# MainBoard.net
KiCad netlist of a schematic drawn in EAGLE
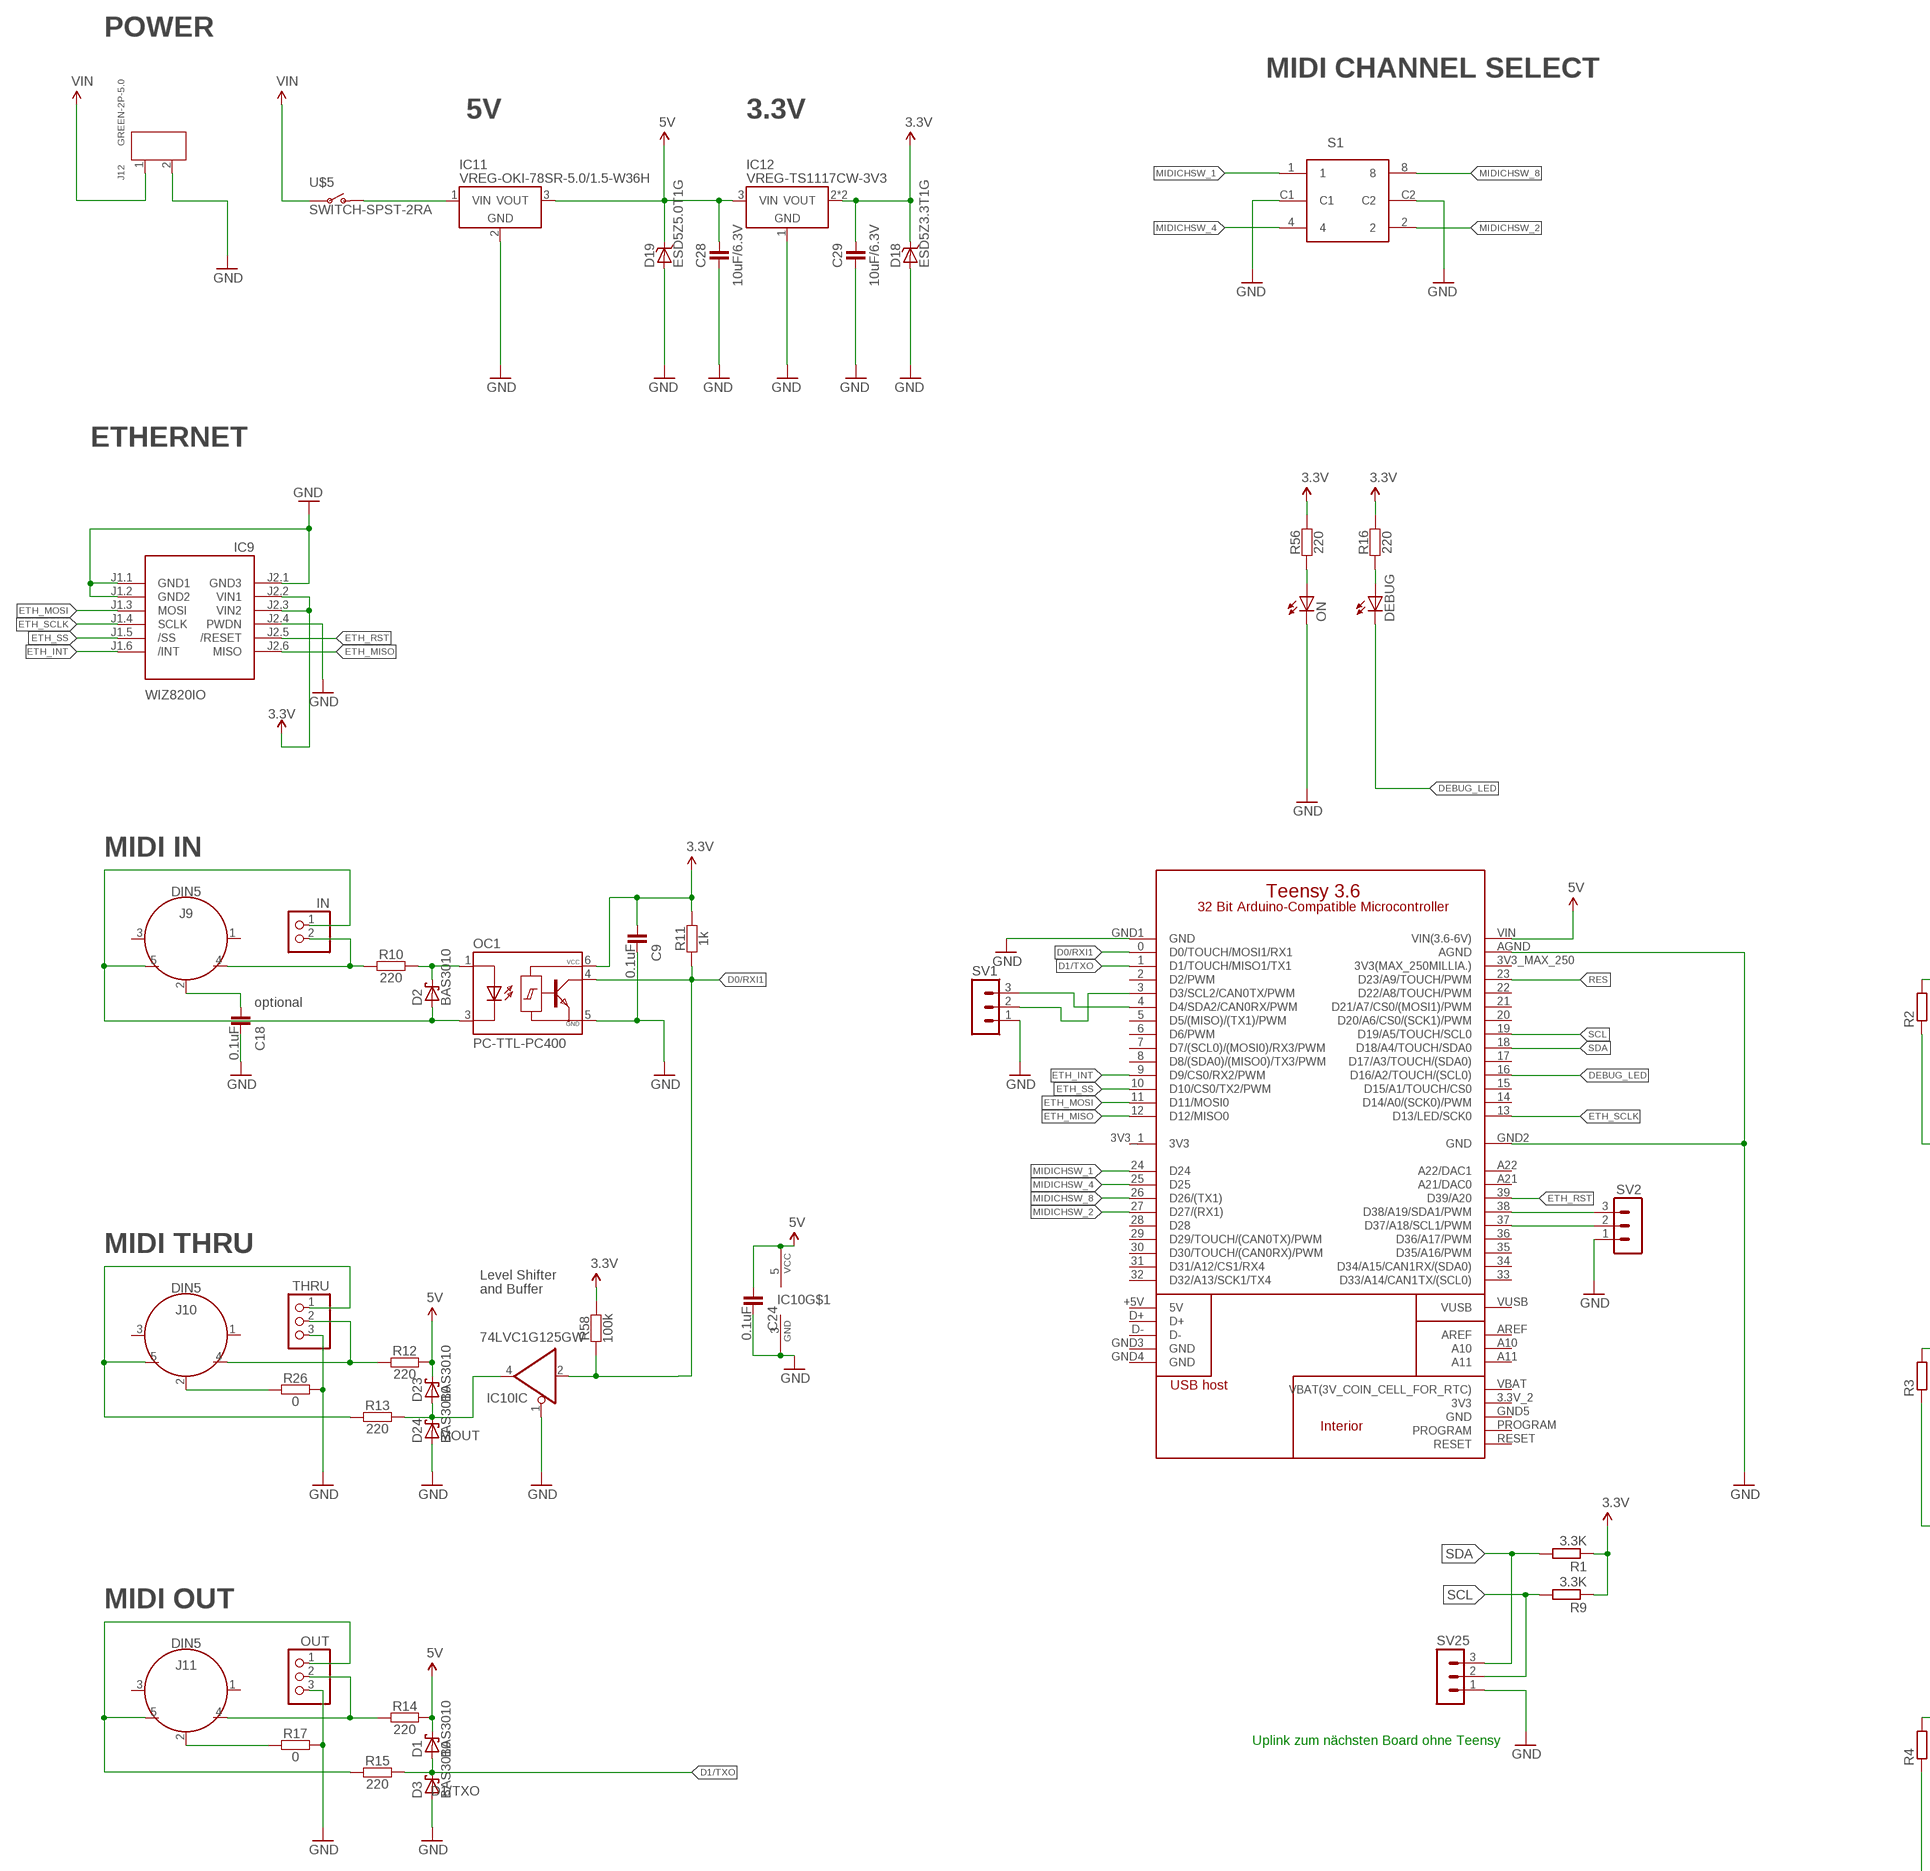
[diagram p0: schematic, sheet 1, part 1 of 2]
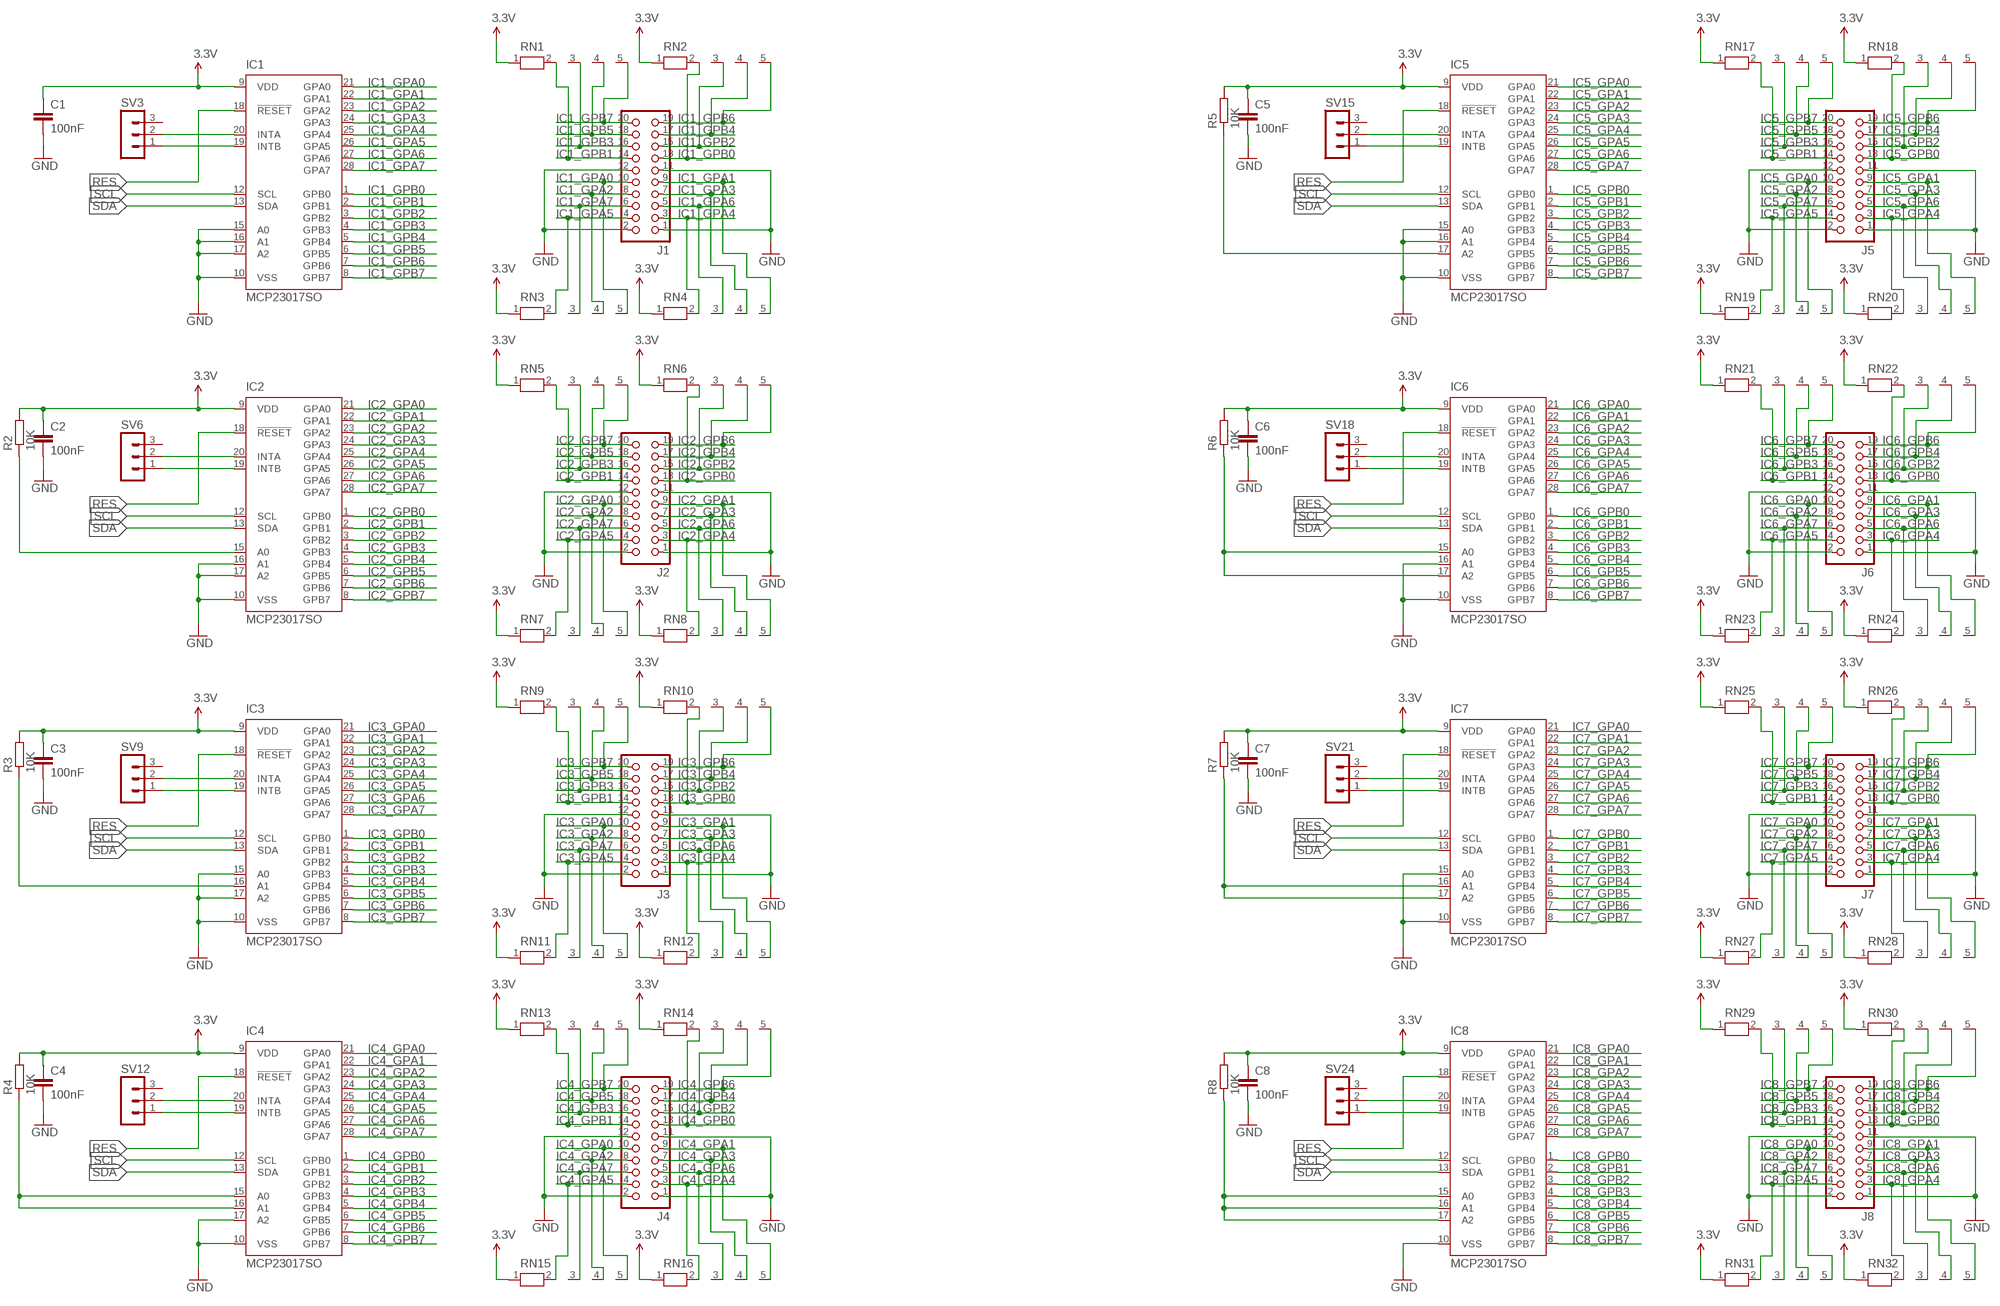
[diagram p1: schematic, sheet 1, part 2 of 2]

(export (version "E")
  (design (tool "Eeschema 10.0.6"))
  (components
    (comp (ref "C1")
      (value "100nF")
      (footprint "eagle-import:C0805")
      (libsource (lib "eagle-import") (part "C-EUC0805"))
    )
    (comp (ref "C2")
      (value "100nF")
      (footprint "eagle-import:C0805")
      (libsource (lib "eagle-import") (part "C-EUC0805"))
    )
    (comp (ref "C3")
      (value "100nF")
      (footprint "eagle-import:C0805")
      (libsource (lib "eagle-import") (part "C-EUC0805"))
    )
    (comp (ref "C4")
      (value "100nF")
      (footprint "eagle-import:C0805")
      (libsource (lib "eagle-import") (part "C-EUC0805"))
    )
    (comp (ref "C5")
      (value "100nF")
      (footprint "eagle-import:C0805")
      (libsource (lib "eagle-import") (part "C-EUC0805"))
    )
    (comp (ref "C6")
      (value "100nF")
      (footprint "eagle-import:C0805")
      (libsource (lib "eagle-import") (part "C-EUC0805"))
    )
    (comp (ref "C7")
      (value "100nF")
      (footprint "eagle-import:C0805")
      (libsource (lib "eagle-import") (part "C-EUC0805"))
    )
    (comp (ref "C8")
      (value "100nF")
      (footprint "eagle-import:C0805")
      (libsource (lib "eagle-import") (part "C-EUC0805"))
    )
    (comp (ref "C9")
      (value "0.1uF")
      (footprint "eagle-import:C0805")
      (fields (field (name "MPN") "CC0603KRX7R7BB104"))
      (libsource (lib "eagle-import") (part "CAPACITOR-0805"))
    )
    (comp (ref "C18")
      (value "0.1uF")
      (footprint "eagle-import:C0805")
      (fields (field (name "MPN") "CC0603KRX7R7BB104"))
      (libsource (lib "eagle-import") (part "CAPACITOR-0805"))
    )
    (comp (ref "C24")
      (value "0.1uF")
      (footprint "eagle-import:C0805")
      (fields (field (name "MPN") "CC0603KRX7R7BB104"))
      (libsource (lib "eagle-import") (part "CAPACITOR-0805"))
    )
    (comp (ref "C28")
      (value "10uF/6.3V")
      (footprint "eagle-import:C0805")
      (libsource (lib "eagle-import") (part "CAPACITOR-0805"))
    )
    (comp (ref "C29")
      (value "10uF/6.3V")
      (footprint "eagle-import:C0805")
      (libsource (lib "eagle-import") (part "CAPACITOR-0805"))
    )
    (comp (ref "D1")
      (value "BAS3010")
      (footprint "eagle-import:SOD323")
      (libsource (lib "eagle-import") (part "D_SCHOTTKY-SOD323"))
    )
    (comp (ref "D2")
      (value "BAS3010")
      (footprint "eagle-import:SOD323")
      (libsource (lib "eagle-import") (part "D_SCHOTTKY-SOD323"))
    )
    (comp (ref "D3")
      (value "BAS3010")
      (footprint "eagle-import:SOD323")
      (libsource (lib "eagle-import") (part "D_SCHOTTKY-SOD323"))
    )
    (comp (ref "D18")
      (value "ESD5Z3.3T1G")
      (footprint "eagle-import:SOD523")
      (libsource (lib "eagle-import") (part "D_TVS-SOD523"))
    )
    (comp (ref "D19")
      (value "ESD5Z5.0T1G")
      (footprint "eagle-import:SOD523")
      (libsource (lib "eagle-import") (part "D_TVS-SOD523"))
    )
    (comp (ref "D23")
      (value "BAS3010")
      (footprint "eagle-import:SOD323")
      (libsource (lib "eagle-import") (part "D_SCHOTTKY-SOD323"))
    )
    (comp (ref "D24")
      (value "BAS3010")
      (footprint "eagle-import:SOD323")
      (libsource (lib "eagle-import") (part "D_SCHOTTKY-SOD323"))
    )
    (comp (ref "DEBUG")
      (value "Red")
      (footprint "eagle-import:LED_3MM")
      (libsource (lib "eagle-import") (part "LED-3MM"))
    )
    (comp (ref "IC1")
      (value "MCP23017SO")
      (footprint "eagle-import:SO28W")
      (fields (field (name "MF") "MICROCHIP") (field (name "MPN") "MCP23017-E/SO"))
      (libsource (lib "eagle-import") (part "MCP23017SO"))
    )
    (comp (ref "IC2")
      (value "MCP23017SO")
      (footprint "eagle-import:SO28W")
      (fields (field (name "MF") "MICROCHIP") (field (name "MPN") "MCP23017-E/SO"))
      (libsource (lib "eagle-import") (part "MCP23017SO"))
    )
    (comp (ref "IC3")
      (value "MCP23017SO")
      (footprint "eagle-import:SO28W")
      (fields (field (name "MF") "MICROCHIP") (field (name "MPN") "MCP23017-E/SO"))
      (libsource (lib "eagle-import") (part "MCP23017SO"))
    )
    (comp (ref "IC4")
      (value "MCP23017SO")
      (footprint "eagle-import:SO28W")
      (fields (field (name "MF") "MICROCHIP") (field (name "MPN") "MCP23017-E/SO"))
      (libsource (lib "eagle-import") (part "MCP23017SO"))
    )
    (comp (ref "IC5")
      (value "MCP23017SO")
      (footprint "eagle-import:SO28W")
      (fields (field (name "MF") "MICROCHIP") (field (name "MPN") "MCP23017-E/SO"))
      (libsource (lib "eagle-import") (part "MCP23017SO"))
    )
    (comp (ref "IC6")
      (value "MCP23017SO")
      (footprint "eagle-import:SO28W")
      (fields (field (name "MF") "MICROCHIP") (field (name "MPN") "MCP23017-E/SO"))
      (libsource (lib "eagle-import") (part "MCP23017SO"))
    )
    (comp (ref "IC7")
      (value "MCP23017SO")
      (footprint "eagle-import:SO28W")
      (fields (field (name "MF") "MICROCHIP") (field (name "MPN") "MCP23017-E/SO"))
      (libsource (lib "eagle-import") (part "MCP23017SO"))
    )
    (comp (ref "IC8")
      (value "MCP23017SO")
      (footprint "eagle-import:SO28W")
      (fields (field (name "MF") "MICROCHIP") (field (name "MPN") "MCP23017-E/SO"))
      (libsource (lib "eagle-import") (part "MCP23017SO"))
    )
    (comp (ref "IC9")
      (value "WIZ820IO_DEVICE'DUAL-IN-LINE'")
      (footprint "eagle-import:WIZ820IO")
      (libsource (lib "eagle-import") (part "WIZ820IO_DEVICE'DUAL-IN-LINE'"))
    )
    (comp (ref "IC10")
      (value "74LVC1G125GW")
      (footprint "eagle-import:SOT353")
      (fields (field (name "MPN") "74HCT1G125GW,125"))
      (libsource (lib "eagle-import") (part "74HCT1G125GW"))
    )
    (comp (ref "IC11")
      (value "VREG-OKI-78SR-5.0/1.5-W36H")
      (footprint "eagle-import:OKI-78SR-H")
      (libsource (lib "eagle-import") (part "VREG-OKI-78SR-5.0/1.5-W36H"))
    )
    (comp (ref "IC12")
      (value "VREG-TS1117CW-3V3")
      (footprint "eagle-import:SOT223")
      (libsource (lib "eagle-import") (part "VREG-TS1117CW-3V3"))
    )
    (comp (ref "IN")
      (value "PINHD-1X2")
      (footprint "eagle-import:1X02")
      (libsource (lib "eagle-import") (part "PINHD-1X2"))
    )
    (comp (ref "J1")
      (value "CON_HEADER_2X10-SHROUDED")
      (footprint "eagle-import:PINSHRD_PTH_2X10")
      (libsource (lib "eagle-import") (part "CON_HEADER_2X10-SHROUDED"))
    )
    (comp (ref "J2")
      (value "CON_HEADER_2X10-SHROUDED")
      (footprint "eagle-import:PINSHRD_PTH_2X10")
      (libsource (lib "eagle-import") (part "CON_HEADER_2X10-SHROUDED"))
    )
    (comp (ref "J3")
      (value "CON_HEADER_2X10-SHROUDED")
      (footprint "eagle-import:PINSHRD_PTH_2X10")
      (libsource (lib "eagle-import") (part "CON_HEADER_2X10-SHROUDED"))
    )
    (comp (ref "J4")
      (value "CON_HEADER_2X10-SHROUDED")
      (footprint "eagle-import:PINSHRD_PTH_2X10")
      (libsource (lib "eagle-import") (part "CON_HEADER_2X10-SHROUDED"))
    )
    (comp (ref "J5")
      (value "CON_HEADER_2X10-SHROUDED")
      (footprint "eagle-import:PINSHRD_PTH_2X10")
      (libsource (lib "eagle-import") (part "CON_HEADER_2X10-SHROUDED"))
    )
    (comp (ref "J6")
      (value "CON_HEADER_2X10-SHROUDED")
      (footprint "eagle-import:PINSHRD_PTH_2X10")
      (libsource (lib "eagle-import") (part "CON_HEADER_2X10-SHROUDED"))
    )
    (comp (ref "J7")
      (value "CON_HEADER_2X10-SHROUDED")
      (footprint "eagle-import:PINSHRD_PTH_2X10")
      (libsource (lib "eagle-import") (part "CON_HEADER_2X10-SHROUDED"))
    )
    (comp (ref "J8")
      (value "CON_HEADER_2X10-SHROUDED")
      (footprint "eagle-import:PINSHRD_PTH_2X10")
      (libsource (lib "eagle-import") (part "CON_HEADER_2X10-SHROUDED"))
    )
    (comp (ref "J9")
      (value "DIN5")
      (footprint "eagle-import:DIN5-RA-PTH")
      (libsource (lib "eagle-import") (part "DIN5"))
    )
    (comp (ref "J10")
      (value "DIN5")
      (footprint "eagle-import:DIN5-RA-PTH")
      (libsource (lib "eagle-import") (part "DIN5"))
    )
    (comp (ref "J11")
      (value "DIN5")
      (footprint "eagle-import:DIN5-RA-PTH")
      (libsource (lib "eagle-import") (part "DIN5"))
    )
    (comp (ref "J12")
      (value "GREEN-2P-5.0")
      (footprint "eagle-import:H2-5.0-10.5X8.0MM")
      (libsource (lib "eagle-import") (part "SCREW-TERMINAL-GREEN(2P-5.0)"))
    )
    (comp (ref "OC1")
      (value "PC-TTL-PC400")
      (footprint "eagle-import:MINIFLAT5")
      (fields (field (name "MPN") "PC400J00000F"))
      (libsource (lib "eagle-import") (part "PC-TTL-PC400"))
    )
    (comp (ref "ON")
      (value "Red")
      (footprint "eagle-import:LED_3MM")
      (libsource (lib "eagle-import") (part "LED-3MM"))
    )
    (comp (ref "OUT")
      (value "PINHD-1X3")
      (footprint "eagle-import:1X03")
      (libsource (lib "eagle-import") (part "PINHD-1X3"))
    )
    (comp (ref "R1")
      (value "3.3K")
      (footprint "eagle-import:R0805")
      (libsource (lib "eagle-import") (part "R-EU_R0805"))
    )
    (comp (ref "R2")
      (value "10K")
      (footprint "eagle-import:R0805")
      (libsource (lib "eagle-import") (part "R-EU_R0805"))
    )
    (comp (ref "R3")
      (value "10K")
      (footprint "eagle-import:R0805")
      (libsource (lib "eagle-import") (part "R-EU_R0805"))
    )
    (comp (ref "R4")
      (value "10K")
      (footprint "eagle-import:R0805")
      (libsource (lib "eagle-import") (part "R-EU_R0805"))
    )
    (comp (ref "R5")
      (value "10K")
      (footprint "eagle-import:R0805")
      (libsource (lib "eagle-import") (part "R-EU_R0805"))
    )
    (comp (ref "R6")
      (value "10K")
      (footprint "eagle-import:R0805")
      (libsource (lib "eagle-import") (part "R-EU_R0805"))
    )
    (comp (ref "R7")
      (value "10K")
      (footprint "eagle-import:R0805")
      (libsource (lib "eagle-import") (part "R-EU_R0805"))
    )
    (comp (ref "R8")
      (value "10K")
      (footprint "eagle-import:R0805")
      (libsource (lib "eagle-import") (part "R-EU_R0805"))
    )
    (comp (ref "R9")
      (value "3.3K")
      (footprint "eagle-import:R0805")
      (libsource (lib "eagle-import") (part "R-EU_R0805"))
    )
    (comp (ref "R10")
      (value "220")
      (footprint "eagle-import:C0805")
      (libsource (lib "eagle-import") (part "RESISTOR-0805"))
    )
    (comp (ref "R11")
      (value "1k")
      (footprint "eagle-import:C0805")
      (libsource (lib "eagle-import") (part "RESISTOR-0805"))
    )
    (comp (ref "R12")
      (value "220")
      (footprint "eagle-import:C0805")
      (fields (field (name "PARTNO") "ERJ-3EKF2200V"))
      (libsource (lib "eagle-import") (part "RESISTOR-0805"))
    )
    (comp (ref "R13")
      (value "220")
      (footprint "eagle-import:C0805")
      (fields (field (name "PARTNO") "ERJ-3EKF2200V"))
      (libsource (lib "eagle-import") (part "RESISTOR-0805"))
    )
    (comp (ref "R14")
      (value "220")
      (footprint "eagle-import:C0805")
      (fields (field (name "PARTNO") "ERJ-3EKF2200V"))
      (libsource (lib "eagle-import") (part "RESISTOR-0805"))
    )
    (comp (ref "R15")
      (value "220")
      (footprint "eagle-import:C0805")
      (fields (field (name "PARTNO") "ERJ-3EKF2200V"))
      (libsource (lib "eagle-import") (part "RESISTOR-0805"))
    )
    (comp (ref "R16")
      (value "220")
      (footprint "eagle-import:C0805")
      (libsource (lib "eagle-import") (part "RESISTOR-0805"))
    )
    (comp (ref "R17")
      (value "0")
      (footprint "eagle-import:C0805")
      (libsource (lib "eagle-import") (part "RESISTOR-0805"))
    )
    (comp (ref "R26")
      (value "0")
      (footprint "eagle-import:C0805")
      (libsource (lib "eagle-import") (part "RESISTOR-0805"))
    )
    (comp (ref "R56")
      (value "220")
      (footprint "eagle-import:C0805")
      (libsource (lib "eagle-import") (part "RESISTOR-0805"))
    )
    (comp (ref "R58")
      (value "100k")
      (footprint "eagle-import:C0805")
      (libsource (lib "eagle-import") (part "RESISTOR-0805"))
    )
    (comp (ref "RN1")
      (value "RN04")
      (footprint "eagle-import:RN-5")
      (libsource (lib "eagle-import") (part "RN04"))
    )
    (comp (ref "RN2")
      (value "RN04")
      (footprint "eagle-import:RN-5")
      (libsource (lib "eagle-import") (part "RN04"))
    )
    (comp (ref "RN3")
      (value "RN04")
      (footprint "eagle-import:RN-5")
      (libsource (lib "eagle-import") (part "RN04"))
    )
    (comp (ref "RN4")
      (value "RN04")
      (footprint "eagle-import:RN-5")
      (libsource (lib "eagle-import") (part "RN04"))
    )
    (comp (ref "RN5")
      (value "RN04")
      (footprint "eagle-import:RN-5")
      (libsource (lib "eagle-import") (part "RN04"))
    )
    (comp (ref "RN6")
      (value "RN04")
      (footprint "eagle-import:RN-5")
      (libsource (lib "eagle-import") (part "RN04"))
    )
    (comp (ref "RN7")
      (value "RN04")
      (footprint "eagle-import:RN-5")
      (libsource (lib "eagle-import") (part "RN04"))
    )
    (comp (ref "RN8")
      (value "RN04")
      (footprint "eagle-import:RN-5")
      (libsource (lib "eagle-import") (part "RN04"))
    )
    (comp (ref "RN9")
      (value "RN04")
      (footprint "eagle-import:RN-5")
      (libsource (lib "eagle-import") (part "RN04"))
    )
    (comp (ref "RN10")
      (value "RN04")
      (footprint "eagle-import:RN-5")
      (libsource (lib "eagle-import") (part "RN04"))
    )
    (comp (ref "RN11")
      (value "RN04")
      (footprint "eagle-import:RN-5")
      (libsource (lib "eagle-import") (part "RN04"))
    )
    (comp (ref "RN12")
      (value "RN04")
      (footprint "eagle-import:RN-5")
      (libsource (lib "eagle-import") (part "RN04"))
    )
    (comp (ref "RN13")
      (value "RN04")
      (footprint "eagle-import:RN-5")
      (libsource (lib "eagle-import") (part "RN04"))
    )
    (comp (ref "RN14")
      (value "RN04")
      (footprint "eagle-import:RN-5")
      (libsource (lib "eagle-import") (part "RN04"))
    )
    (comp (ref "RN15")
      (value "RN04")
      (footprint "eagle-import:RN-5")
      (libsource (lib "eagle-import") (part "RN04"))
    )
    (comp (ref "RN16")
      (value "RN04")
      (footprint "eagle-import:RN-5")
      (libsource (lib "eagle-import") (part "RN04"))
    )
    (comp (ref "RN17")
      (value "RN04")
      (footprint "eagle-import:RN-5")
      (libsource (lib "eagle-import") (part "RN04"))
    )
    (comp (ref "RN18")
      (value "RN04")
      (footprint "eagle-import:RN-5")
      (libsource (lib "eagle-import") (part "RN04"))
    )
    (comp (ref "RN19")
      (value "RN04")
      (footprint "eagle-import:RN-5")
      (libsource (lib "eagle-import") (part "RN04"))
    )
    (comp (ref "RN20")
      (value "RN04")
      (footprint "eagle-import:RN-5")
      (libsource (lib "eagle-import") (part "RN04"))
    )
    (comp (ref "RN21")
      (value "RN04")
      (footprint "eagle-import:RN-5")
      (libsource (lib "eagle-import") (part "RN04"))
    )
    (comp (ref "RN22")
      (value "RN04")
      (footprint "eagle-import:RN-5")
      (libsource (lib "eagle-import") (part "RN04"))
    )
    (comp (ref "RN23")
      (value "RN04")
      (footprint "eagle-import:RN-5")
      (libsource (lib "eagle-import") (part "RN04"))
    )
    (comp (ref "RN24")
      (value "RN04")
      (footprint "eagle-import:RN-5")
      (libsource (lib "eagle-import") (part "RN04"))
    )
    (comp (ref "RN25")
      (value "RN04")
      (footprint "eagle-import:RN-5")
      (libsource (lib "eagle-import") (part "RN04"))
    )
    (comp (ref "RN26")
      (value "RN04")
      (footprint "eagle-import:RN-5")
      (libsource (lib "eagle-import") (part "RN04"))
    )
    (comp (ref "RN27")
      (value "RN04")
      (footprint "eagle-import:RN-5")
      (libsource (lib "eagle-import") (part "RN04"))
    )
    (comp (ref "RN28")
      (value "RN04")
      (footprint "eagle-import:RN-5")
      (libsource (lib "eagle-import") (part "RN04"))
    )
    (comp (ref "RN29")
      (value "RN04")
      (footprint "eagle-import:RN-5")
      (libsource (lib "eagle-import") (part "RN04"))
    )
    (comp (ref "RN30")
      (value "RN04")
      (footprint "eagle-import:RN-5")
      (libsource (lib "eagle-import") (part "RN04"))
    )
    (comp (ref "RN31")
      (value "RN04")
      (footprint "eagle-import:RN-5")
      (libsource (lib "eagle-import") (part "RN04"))
    )
    (comp (ref "RN32")
      (value "RN04")
      (footprint "eagle-import:RN-5")
      (libsource (lib "eagle-import") (part "RN04"))
    )
    (comp (ref "S1")
      (value "428521420916")
      (footprint "eagle-import:428521420916")
      (libsource (lib "eagle-import") (part "428521420916"))
    )
    (comp (ref "SV1")
      (value "MA03-1")
      (footprint "eagle-import:MA03-1")
      (libsource (lib "eagle-import") (part "MA03-1"))
    )
    (comp (ref "SV2")
      (value "MA03-1")
      (footprint "eagle-import:MA03-1")
      (libsource (lib "eagle-import") (part "MA03-1"))
    )
    (comp (ref "SV3")
      (value "MA03-1")
      (footprint "eagle-import:MA03-1")
      (libsource (lib "eagle-import") (part "MA03-1"))
    )
    (comp (ref "SV6")
      (value "MA03-1")
      (footprint "eagle-import:MA03-1")
      (libsource (lib "eagle-import") (part "MA03-1"))
    )
    (comp (ref "SV9")
      (value "MA03-1")
      (footprint "eagle-import:MA03-1")
      (libsource (lib "eagle-import") (part "MA03-1"))
    )
    (comp (ref "SV12")
      (value "MA03-1")
      (footprint "eagle-import:MA03-1")
      (libsource (lib "eagle-import") (part "MA03-1"))
    )
    (comp (ref "SV15")
      (value "MA03-1")
      (footprint "eagle-import:MA03-1")
      (libsource (lib "eagle-import") (part "MA03-1"))
    )
    (comp (ref "SV18")
      (value "MA03-1")
      (footprint "eagle-import:MA03-1")
      (libsource (lib "eagle-import") (part "MA03-1"))
    )
    (comp (ref "SV21")
      (value "MA03-1")
      (footprint "eagle-import:MA03-1")
      (libsource (lib "eagle-import") (part "MA03-1"))
    )
    (comp (ref "SV24")
      (value "MA03-1")
      (footprint "eagle-import:MA03-1")
      (libsource (lib "eagle-import") (part "MA03-1"))
    )
    (comp (ref "SV25")
      (value "MA03-1")
      (footprint "eagle-import:MA03-1")
      (libsource (lib "eagle-import") (part "MA03-1"))
    )
    (comp (ref "THRU")
      (value "PINHD-1X3")
      (footprint "eagle-import:1X03")
      (libsource (lib "eagle-import") (part "PINHD-1X3"))
    )
    (comp (ref "U$1")
      (value "TEENSY-3.6_ONLY_HOLES")
      (footprint "eagle-import:TEENSY-3.6_ONLY_HOLES")
      (libsource (lib "eagle-import") (part "TEENSY-3.6_ONLY_HOLES"))
    )
    (comp (ref "U$5")
      (value "SWITCH-SPST-2RA")
      (footprint "eagle-import:R_SW_TH")
      (libsource (lib "eagle-import") (part "SWITCH-SPST-2RA"))
    )
  )
  (nets
    (net (code "1") (name "/3V3") (class "Default")
      (node (ref "U$1") (pin "3V3_1") (pinfunction "3V3_3V3_1") (pintype "power_in"))
    )
    (net (code "2") (name "/IC1_GPA0") (class "Default")
      (node (ref "IC1") (pin "21") (pinfunction "GPA0_21") (pintype "bidirectional"))
      (node (ref "J1") (pin "10") (pinfunction "10_10") (pintype "passive"))
      (node (ref "RN3") (pin "5") (pinfunction "5_5") (pintype "passive"))
    )
    (net (code "3") (name "/IC1_GPA1") (class "Default")
      (node (ref "IC1") (pin "22") (pinfunction "GPA1_22") (pintype "bidirectional"))
      (node (ref "J1") (pin "9") (pinfunction "9_9") (pintype "passive"))
      (node (ref "RN4") (pin "5") (pinfunction "5_5") (pintype "passive"))
    )
    (net (code "4") (name "/IC1_GPA2") (class "Default")
      (node (ref "IC1") (pin "23") (pinfunction "GPA2_23") (pintype "bidirectional"))
      (node (ref "J1") (pin "8") (pinfunction "8_8") (pintype "passive"))
      (node (ref "RN3") (pin "4") (pinfunction "4_4") (pintype "passive"))
    )
    (net (code "5") (name "/IC1_GPA3") (class "Default")
      (node (ref "IC1") (pin "24") (pinfunction "GPA3_24") (pintype "bidirectional"))
      (node (ref "J1") (pin "7") (pinfunction "7_7") (pintype "passive"))
      (node (ref "RN4") (pin "4") (pinfunction "4_4") (pintype "passive"))
    )
    (net (code "6") (name "/IC1_GPA4") (class "Default")
      (node (ref "IC1") (pin "25") (pinfunction "GPA4_25") (pintype "bidirectional"))
      (node (ref "J1") (pin "3") (pinfunction "3_3") (pintype "passive"))
      (node (ref "RN4") (pin "2") (pinfunction "2_2") (pintype "passive"))
    )
    (net (code "7") (name "/IC1_GPA5") (class "Default")
      (node (ref "IC1") (pin "26") (pinfunction "GPA5_26") (pintype "bidirectional"))
      (node (ref "J1") (pin "4") (pinfunction "4_4") (pintype "passive"))
      (node (ref "RN3") (pin "2") (pinfunction "2_2") (pintype "passive"))
    )
    (net (code "8") (name "/IC1_GPA6") (class "Default")
      (node (ref "IC1") (pin "27") (pinfunction "GPA6_27") (pintype "bidirectional"))
      (node (ref "J1") (pin "5") (pinfunction "5_5") (pintype "passive"))
      (node (ref "RN4") (pin "3") (pinfunction "3_3") (pintype "passive"))
    )
    (net (code "9") (name "/IC1_GPA7") (class "Default")
      (node (ref "IC1") (pin "28") (pinfunction "GPA7_28") (pintype "bidirectional"))
      (node (ref "J1") (pin "6") (pinfunction "6_6") (pintype "passive"))
      (node (ref "RN3") (pin "3") (pinfunction "3_3") (pintype "passive"))
    )
    (net (code "10") (name "/IC1_GPB0") (class "Default")
      (node (ref "IC1") (pin "1") (pinfunction "GPB0_1") (pintype "bidirectional"))
      (node (ref "J1") (pin "13") (pinfunction "13_13") (pintype "passive"))
      (node (ref "RN2") (pin "2") (pinfunction "2_2") (pintype "passive"))
    )
    (net (code "11") (name "/IC1_GPB1") (class "Default")
      (node (ref "IC1") (pin "2") (pinfunction "GPB1_2") (pintype "bidirectional"))
      (node (ref "J1") (pin "14") (pinfunction "14_14") (pintype "passive"))
      (node (ref "RN1") (pin "2") (pinfunction "2_2") (pintype "passive"))
    )
    (net (code "12") (name "/IC1_GPB2") (class "Default")
      (node (ref "IC1") (pin "3") (pinfunction "GPB2_3") (pintype "bidirectional"))
      (node (ref "J1") (pin "15") (pinfunction "15_15") (pintype "passive"))
      (node (ref "RN2") (pin "3") (pinfunction "3_3") (pintype "passive"))
    )
    (net (code "13") (name "/IC1_GPB3") (class "Default")
      (node (ref "IC1") (pin "4") (pinfunction "GPB3_4") (pintype "bidirectional"))
      (node (ref "J1") (pin "16") (pinfunction "16_16") (pintype "passive"))
      (node (ref "RN1") (pin "3") (pinfunction "3_3") (pintype "passive"))
    )
    (net (code "14") (name "/IC1_GPB4") (class "Default")
      (node (ref "IC1") (pin "5") (pinfunction "GPB4_5") (pintype "bidirectional"))
      (node (ref "J1") (pin "17") (pinfunction "17_17") (pintype "passive"))
      (node (ref "RN2") (pin "4") (pinfunction "4_4") (pintype "passive"))
    )
    (net (code "15") (name "/IC1_GPB5") (class "Default")
      (node (ref "IC1") (pin "6") (pinfunction "GPB5_6") (pintype "bidirectional"))
      (node (ref "J1") (pin "18") (pinfunction "18_18") (pintype "passive"))
      (node (ref "RN1") (pin "4") (pinfunction "4_4") (pintype "passive"))
    )
    (net (code "16") (name "/IC1_GPB6") (class "Default")
      (node (ref "IC1") (pin "7") (pinfunction "GPB6_7") (pintype "bidirectional"))
      (node (ref "J1") (pin "19") (pinfunction "19_19") (pintype "passive"))
      (node (ref "RN2") (pin "5") (pinfunction "5_5") (pintype "passive"))
    )
    (net (code "17") (name "/IC1_GPB7") (class "Default")
      (node (ref "IC1") (pin "8") (pinfunction "GPB7_8") (pintype "bidirectional"))
      (node (ref "J1") (pin "20") (pinfunction "20_20") (pintype "passive"))
      (node (ref "RN1") (pin "5") (pinfunction "5_5") (pintype "passive"))
    )
    (net (code "18") (name "/IC2_GPA0") (class "Default")
      (node (ref "IC2") (pin "21") (pinfunction "GPA0_21") (pintype "bidirectional"))
      (node (ref "J2") (pin "10") (pinfunction "10_10") (pintype "passive"))
      (node (ref "RN7") (pin "5") (pinfunction "5_5") (pintype "passive"))
    )
    (net (code "19") (name "/IC2_GPA1") (class "Default")
      (node (ref "IC2") (pin "22") (pinfunction "GPA1_22") (pintype "bidirectional"))
      (node (ref "J2") (pin "9") (pinfunction "9_9") (pintype "passive"))
      (node (ref "RN8") (pin "5") (pinfunction "5_5") (pintype "passive"))
    )
    (net (code "20") (name "/IC2_GPA2") (class "Default")
      (node (ref "IC2") (pin "23") (pinfunction "GPA2_23") (pintype "bidirectional"))
      (node (ref "J2") (pin "8") (pinfunction "8_8") (pintype "passive"))
      (node (ref "RN7") (pin "4") (pinfunction "4_4") (pintype "passive"))
    )
    (net (code "21") (name "/IC2_GPA3") (class "Default")
      (node (ref "IC2") (pin "24") (pinfunction "GPA3_24") (pintype "bidirectional"))
      (node (ref "J2") (pin "7") (pinfunction "7_7") (pintype "passive"))
      (node (ref "RN8") (pin "4") (pinfunction "4_4") (pintype "passive"))
    )
    (net (code "22") (name "/IC2_GPA4") (class "Default")
      (node (ref "IC2") (pin "25") (pinfunction "GPA4_25") (pintype "bidirectional"))
      (node (ref "J2") (pin "3") (pinfunction "3_3") (pintype "passive"))
      (node (ref "RN8") (pin "2") (pinfunction "2_2") (pintype "passive"))
    )
    (net (code "23") (name "/IC2_GPA5") (class "Default")
      (node (ref "IC2") (pin "26") (pinfunction "GPA5_26") (pintype "bidirectional"))
      (node (ref "J2") (pin "4") (pinfunction "4_4") (pintype "passive"))
      (node (ref "RN7") (pin "2") (pinfunction "2_2") (pintype "passive"))
    )
    (net (code "24") (name "/IC2_GPA6") (class "Default")
      (node (ref "IC2") (pin "27") (pinfunction "GPA6_27") (pintype "bidirectional"))
      (node (ref "J2") (pin "5") (pinfunction "5_5") (pintype "passive"))
      (node (ref "RN8") (pin "3") (pinfunction "3_3") (pintype "passive"))
    )
    (net (code "25") (name "/IC2_GPA7") (class "Default")
      (node (ref "IC2") (pin "28") (pinfunction "GPA7_28") (pintype "bidirectional"))
      (node (ref "J2") (pin "6") (pinfunction "6_6") (pintype "passive"))
      (node (ref "RN7") (pin "3") (pinfunction "3_3") (pintype "passive"))
    )
    (net (code "26") (name "/IC2_GPB0") (class "Default")
      (node (ref "IC2") (pin "1") (pinfunction "GPB0_1") (pintype "bidirectional"))
      (node (ref "J2") (pin "13") (pinfunction "13_13") (pintype "passive"))
      (node (ref "RN6") (pin "2") (pinfunction "2_2") (pintype "passive"))
    )
    (net (code "27") (name "/IC2_GPB1") (class "Default")
      (node (ref "IC2") (pin "2") (pinfunction "GPB1_2") (pintype "bidirectional"))
      (node (ref "J2") (pin "14") (pinfunction "14_14") (pintype "passive"))
      (node (ref "RN5") (pin "2") (pinfunction "2_2") (pintype "passive"))
    )
    (net (code "28") (name "/IC2_GPB2") (class "Default")
      (node (ref "IC2") (pin "3") (pinfunction "GPB2_3") (pintype "bidirectional"))
      (node (ref "J2") (pin "15") (pinfunction "15_15") (pintype "passive"))
      (node (ref "RN6") (pin "3") (pinfunction "3_3") (pintype "passive"))
    )
    (net (code "29") (name "/IC2_GPB3") (class "Default")
      (node (ref "IC2") (pin "4") (pinfunction "GPB3_4") (pintype "bidirectional"))
      (node (ref "J2") (pin "16") (pinfunction "16_16") (pintype "passive"))
      (node (ref "RN5") (pin "3") (pinfunction "3_3") (pintype "passive"))
    )
    (net (code "30") (name "/IC2_GPB4") (class "Default")
      (node (ref "IC2") (pin "5") (pinfunction "GPB4_5") (pintype "bidirectional"))
      (node (ref "J2") (pin "17") (pinfunction "17_17") (pintype "passive"))
      (node (ref "RN6") (pin "4") (pinfunction "4_4") (pintype "passive"))
    )
    (net (code "31") (name "/IC2_GPB5") (class "Default")
      (node (ref "IC2") (pin "6") (pinfunction "GPB5_6") (pintype "bidirectional"))
      (node (ref "J2") (pin "18") (pinfunction "18_18") (pintype "passive"))
      (node (ref "RN5") (pin "4") (pinfunction "4_4") (pintype "passive"))
    )
    (net (code "32") (name "/IC2_GPB6") (class "Default")
      (node (ref "IC2") (pin "7") (pinfunction "GPB6_7") (pintype "bidirectional"))
      (node (ref "J2") (pin "19") (pinfunction "19_19") (pintype "passive"))
      (node (ref "RN6") (pin "5") (pinfunction "5_5") (pintype "passive"))
    )
    (net (code "33") (name "/IC2_GPB7") (class "Default")
      (node (ref "IC2") (pin "8") (pinfunction "GPB7_8") (pintype "bidirectional"))
      (node (ref "J2") (pin "20") (pinfunction "20_20") (pintype "passive"))
      (node (ref "RN5") (pin "5") (pinfunction "5_5") (pintype "passive"))
    )
    (net (code "34") (name "/IC3_GPA0") (class "Default")
      (node (ref "IC3") (pin "21") (pinfunction "GPA0_21") (pintype "bidirectional"))
      (node (ref "J3") (pin "10") (pinfunction "10_10") (pintype "passive"))
      (node (ref "RN11") (pin "5") (pinfunction "5_5") (pintype "passive"))
    )
    (net (code "35") (name "/IC3_GPA1") (class "Default")
      (node (ref "IC3") (pin "22") (pinfunction "GPA1_22") (pintype "bidirectional"))
      (node (ref "J3") (pin "9") (pinfunction "9_9") (pintype "passive"))
      (node (ref "RN12") (pin "5") (pinfunction "5_5") (pintype "passive"))
    )
    (net (code "36") (name "/IC3_GPA2") (class "Default")
      (node (ref "IC3") (pin "23") (pinfunction "GPA2_23") (pintype "bidirectional"))
      (node (ref "J3") (pin "8") (pinfunction "8_8") (pintype "passive"))
      (node (ref "RN11") (pin "4") (pinfunction "4_4") (pintype "passive"))
    )
    (net (code "37") (name "/IC3_GPA3") (class "Default")
      (node (ref "IC3") (pin "24") (pinfunction "GPA3_24") (pintype "bidirectional"))
      (node (ref "J3") (pin "7") (pinfunction "7_7") (pintype "passive"))
      (node (ref "RN12") (pin "4") (pinfunction "4_4") (pintype "passive"))
    )
    (net (code "38") (name "/IC3_GPA4") (class "Default")
      (node (ref "IC3") (pin "25") (pinfunction "GPA4_25") (pintype "bidirectional"))
      (node (ref "J3") (pin "3") (pinfunction "3_3") (pintype "passive"))
      (node (ref "RN12") (pin "2") (pinfunction "2_2") (pintype "passive"))
    )
    (net (code "39") (name "/IC3_GPA5") (class "Default")
      (node (ref "IC3") (pin "26") (pinfunction "GPA5_26") (pintype "bidirectional"))
      (node (ref "J3") (pin "4") (pinfunction "4_4") (pintype "passive"))
      (node (ref "RN11") (pin "2") (pinfunction "2_2") (pintype "passive"))
    )
    (net (code "40") (name "/IC3_GPA6") (class "Default")
      (node (ref "IC3") (pin "27") (pinfunction "GPA6_27") (pintype "bidirectional"))
      (node (ref "J3") (pin "5") (pinfunction "5_5") (pintype "passive"))
      (node (ref "RN12") (pin "3") (pinfunction "3_3") (pintype "passive"))
    )
    (net (code "41") (name "/IC3_GPA7") (class "Default")
      (node (ref "IC3") (pin "28") (pinfunction "GPA7_28") (pintype "bidirectional"))
      (node (ref "J3") (pin "6") (pinfunction "6_6") (pintype "passive"))
      (node (ref "RN11") (pin "3") (pinfunction "3_3") (pintype "passive"))
    )
    (net (code "42") (name "/IC3_GPB0") (class "Default")
      (node (ref "IC3") (pin "1") (pinfunction "GPB0_1") (pintype "bidirectional"))
      (node (ref "J3") (pin "13") (pinfunction "13_13") (pintype "passive"))
      (node (ref "RN10") (pin "2") (pinfunction "2_2") (pintype "passive"))
    )
    (net (code "43") (name "/IC3_GPB1") (class "Default")
      (node (ref "IC3") (pin "2") (pinfunction "GPB1_2") (pintype "bidirectional"))
      (node (ref "J3") (pin "14") (pinfunction "14_14") (pintype "passive"))
      (node (ref "RN9") (pin "2") (pinfunction "2_2") (pintype "passive"))
    )
    (net (code "44") (name "/IC3_GPB2") (class "Default")
      (node (ref "IC3") (pin "3") (pinfunction "GPB2_3") (pintype "bidirectional"))
      (node (ref "J3") (pin "15") (pinfunction "15_15") (pintype "passive"))
      (node (ref "RN10") (pin "3") (pinfunction "3_3") (pintype "passive"))
    )
    (net (code "45") (name "/IC3_GPB3") (class "Default")
      (node (ref "IC3") (pin "4") (pinfunction "GPB3_4") (pintype "bidirectional"))
      (node (ref "J3") (pin "16") (pinfunction "16_16") (pintype "passive"))
      (node (ref "RN9") (pin "3") (pinfunction "3_3") (pintype "passive"))
    )
    (net (code "46") (name "/IC3_GPB4") (class "Default")
      (node (ref "IC3") (pin "5") (pinfunction "GPB4_5") (pintype "bidirectional"))
      (node (ref "J3") (pin "17") (pinfunction "17_17") (pintype "passive"))
      (node (ref "RN10") (pin "4") (pinfunction "4_4") (pintype "passive"))
    )
    (net (code "47") (name "/IC3_GPB5") (class "Default")
      (node (ref "IC3") (pin "6") (pinfunction "GPB5_6") (pintype "bidirectional"))
      (node (ref "J3") (pin "18") (pinfunction "18_18") (pintype "passive"))
      (node (ref "RN9") (pin "4") (pinfunction "4_4") (pintype "passive"))
    )
    (net (code "48") (name "/IC3_GPB6") (class "Default")
      (node (ref "IC3") (pin "7") (pinfunction "GPB6_7") (pintype "bidirectional"))
      (node (ref "J3") (pin "19") (pinfunction "19_19") (pintype "passive"))
      (node (ref "RN10") (pin "5") (pinfunction "5_5") (pintype "passive"))
    )
    (net (code "49") (name "/IC3_GPB7") (class "Default")
      (node (ref "IC3") (pin "8") (pinfunction "GPB7_8") (pintype "bidirectional"))
      (node (ref "J3") (pin "20") (pinfunction "20_20") (pintype "passive"))
      (node (ref "RN9") (pin "5") (pinfunction "5_5") (pintype "passive"))
    )
    (net (code "50") (name "/IC4_GPA0") (class "Default")
      (node (ref "IC4") (pin "21") (pinfunction "GPA0_21") (pintype "bidirectional"))
      (node (ref "J4") (pin "10") (pinfunction "10_10") (pintype "passive"))
      (node (ref "RN15") (pin "5") (pinfunction "5_5") (pintype "passive"))
    )
    (net (code "51") (name "/IC4_GPA1") (class "Default")
      (node (ref "IC4") (pin "22") (pinfunction "GPA1_22") (pintype "bidirectional"))
      (node (ref "J4") (pin "9") (pinfunction "9_9") (pintype "passive"))
      (node (ref "RN16") (pin "5") (pinfunction "5_5") (pintype "passive"))
    )
    (net (code "52") (name "/IC4_GPA2") (class "Default")
      (node (ref "IC4") (pin "23") (pinfunction "GPA2_23") (pintype "bidirectional"))
      (node (ref "J4") (pin "8") (pinfunction "8_8") (pintype "passive"))
      (node (ref "RN15") (pin "4") (pinfunction "4_4") (pintype "passive"))
    )
    (net (code "53") (name "/IC4_GPA3") (class "Default")
      (node (ref "IC4") (pin "24") (pinfunction "GPA3_24") (pintype "bidirectional"))
      (node (ref "J4") (pin "7") (pinfunction "7_7") (pintype "passive"))
      (node (ref "RN16") (pin "4") (pinfunction "4_4") (pintype "passive"))
    )
    (net (code "54") (name "/IC4_GPA4") (class "Default")
      (node (ref "IC4") (pin "25") (pinfunction "GPA4_25") (pintype "bidirectional"))
      (node (ref "J4") (pin "3") (pinfunction "3_3") (pintype "passive"))
      (node (ref "RN16") (pin "2") (pinfunction "2_2") (pintype "passive"))
    )
    (net (code "55") (name "/IC4_GPA5") (class "Default")
      (node (ref "IC4") (pin "26") (pinfunction "GPA5_26") (pintype "bidirectional"))
      (node (ref "J4") (pin "4") (pinfunction "4_4") (pintype "passive"))
      (node (ref "RN15") (pin "2") (pinfunction "2_2") (pintype "passive"))
    )
    (net (code "56") (name "/IC4_GPA6") (class "Default")
      (node (ref "IC4") (pin "27") (pinfunction "GPA6_27") (pintype "bidirectional"))
      (node (ref "J4") (pin "5") (pinfunction "5_5") (pintype "passive"))
      (node (ref "RN16") (pin "3") (pinfunction "3_3") (pintype "passive"))
    )
    (net (code "57") (name "/IC4_GPA7") (class "Default")
      (node (ref "IC4") (pin "28") (pinfunction "GPA7_28") (pintype "bidirectional"))
      (node (ref "J4") (pin "6") (pinfunction "6_6") (pintype "passive"))
      (node (ref "RN15") (pin "3") (pinfunction "3_3") (pintype "passive"))
    )
    (net (code "58") (name "/IC4_GPB0") (class "Default")
      (node (ref "IC4") (pin "1") (pinfunction "GPB0_1") (pintype "bidirectional"))
      (node (ref "J4") (pin "13") (pinfunction "13_13") (pintype "passive"))
      (node (ref "RN14") (pin "2") (pinfunction "2_2") (pintype "passive"))
    )
    (net (code "59") (name "/IC4_GPB1") (class "Default")
      (node (ref "IC4") (pin "2") (pinfunction "GPB1_2") (pintype "bidirectional"))
      (node (ref "J4") (pin "14") (pinfunction "14_14") (pintype "passive"))
      (node (ref "RN13") (pin "2") (pinfunction "2_2") (pintype "passive"))
    )
    (net (code "60") (name "/IC4_GPB2") (class "Default")
      (node (ref "IC4") (pin "3") (pinfunction "GPB2_3") (pintype "bidirectional"))
      (node (ref "J4") (pin "15") (pinfunction "15_15") (pintype "passive"))
      (node (ref "RN14") (pin "3") (pinfunction "3_3") (pintype "passive"))
    )
    (net (code "61") (name "/IC4_GPB3") (class "Default")
      (node (ref "IC4") (pin "4") (pinfunction "GPB3_4") (pintype "bidirectional"))
      (node (ref "J4") (pin "16") (pinfunction "16_16") (pintype "passive"))
      (node (ref "RN13") (pin "3") (pinfunction "3_3") (pintype "passive"))
    )
    (net (code "62") (name "/IC4_GPB4") (class "Default")
      (node (ref "IC4") (pin "5") (pinfunction "GPB4_5") (pintype "bidirectional"))
      (node (ref "J4") (pin "17") (pinfunction "17_17") (pintype "passive"))
      (node (ref "RN14") (pin "4") (pinfunction "4_4") (pintype "passive"))
    )
    (net (code "63") (name "/IC4_GPB5") (class "Default")
      (node (ref "IC4") (pin "6") (pinfunction "GPB5_6") (pintype "bidirectional"))
      (node (ref "J4") (pin "18") (pinfunction "18_18") (pintype "passive"))
      (node (ref "RN13") (pin "4") (pinfunction "4_4") (pintype "passive"))
    )
    (net (code "64") (name "/IC4_GPB6") (class "Default")
      (node (ref "IC4") (pin "7") (pinfunction "GPB6_7") (pintype "bidirectional"))
      (node (ref "J4") (pin "19") (pinfunction "19_19") (pintype "passive"))
      (node (ref "RN14") (pin "5") (pinfunction "5_5") (pintype "passive"))
    )
    (net (code "65") (name "/IC4_GPB7") (class "Default")
      (node (ref "IC4") (pin "8") (pinfunction "GPB7_8") (pintype "bidirectional"))
      (node (ref "J4") (pin "20") (pinfunction "20_20") (pintype "passive"))
      (node (ref "RN13") (pin "5") (pinfunction "5_5") (pintype "passive"))
    )
    (net (code "66") (name "/IC5_GPA0") (class "Default")
      (node (ref "IC5") (pin "21") (pinfunction "GPA0_21") (pintype "bidirectional"))
      (node (ref "J5") (pin "10") (pinfunction "10_10") (pintype "passive"))
      (node (ref "RN19") (pin "5") (pinfunction "5_5") (pintype "passive"))
    )
    (net (code "67") (name "/IC5_GPA1") (class "Default")
      (node (ref "IC5") (pin "22") (pinfunction "GPA1_22") (pintype "bidirectional"))
      (node (ref "J5") (pin "9") (pinfunction "9_9") (pintype "passive"))
      (node (ref "RN20") (pin "5") (pinfunction "5_5") (pintype "passive"))
    )
    (net (code "68") (name "/IC5_GPA2") (class "Default")
      (node (ref "IC5") (pin "23") (pinfunction "GPA2_23") (pintype "bidirectional"))
      (node (ref "J5") (pin "8") (pinfunction "8_8") (pintype "passive"))
      (node (ref "RN19") (pin "4") (pinfunction "4_4") (pintype "passive"))
    )
    (net (code "69") (name "/IC5_GPA3") (class "Default")
      (node (ref "IC5") (pin "24") (pinfunction "GPA3_24") (pintype "bidirectional"))
      (node (ref "J5") (pin "7") (pinfunction "7_7") (pintype "passive"))
      (node (ref "RN20") (pin "4") (pinfunction "4_4") (pintype "passive"))
    )
    (net (code "70") (name "/IC5_GPA4") (class "Default")
      (node (ref "IC5") (pin "25") (pinfunction "GPA4_25") (pintype "bidirectional"))
      (node (ref "J5") (pin "3") (pinfunction "3_3") (pintype "passive"))
      (node (ref "RN20") (pin "2") (pinfunction "2_2") (pintype "passive"))
    )
    (net (code "71") (name "/IC5_GPA5") (class "Default")
      (node (ref "IC5") (pin "26") (pinfunction "GPA5_26") (pintype "bidirectional"))
      (node (ref "J5") (pin "4") (pinfunction "4_4") (pintype "passive"))
      (node (ref "RN19") (pin "2") (pinfunction "2_2") (pintype "passive"))
    )
    (net (code "72") (name "/IC5_GPA6") (class "Default")
      (node (ref "IC5") (pin "27") (pinfunction "GPA6_27") (pintype "bidirectional"))
      (node (ref "J5") (pin "5") (pinfunction "5_5") (pintype "passive"))
      (node (ref "RN20") (pin "3") (pinfunction "3_3") (pintype "passive"))
    )
    (net (code "73") (name "/IC5_GPA7") (class "Default")
      (node (ref "IC5") (pin "28") (pinfunction "GPA7_28") (pintype "bidirectional"))
      (node (ref "J5") (pin "6") (pinfunction "6_6") (pintype "passive"))
      (node (ref "RN19") (pin "3") (pinfunction "3_3") (pintype "passive"))
    )
    (net (code "74") (name "/IC5_GPB0") (class "Default")
      (node (ref "IC5") (pin "1") (pinfunction "GPB0_1") (pintype "bidirectional"))
      (node (ref "J5") (pin "13") (pinfunction "13_13") (pintype "passive"))
      (node (ref "RN18") (pin "2") (pinfunction "2_2") (pintype "passive"))
    )
    (net (code "75") (name "/IC5_GPB1") (class "Default")
      (node (ref "IC5") (pin "2") (pinfunction "GPB1_2") (pintype "bidirectional"))
      (node (ref "J5") (pin "14") (pinfunction "14_14") (pintype "passive"))
      (node (ref "RN17") (pin "2") (pinfunction "2_2") (pintype "passive"))
    )
    (net (code "76") (name "/IC5_GPB2") (class "Default")
      (node (ref "IC5") (pin "3") (pinfunction "GPB2_3") (pintype "bidirectional"))
      (node (ref "J5") (pin "15") (pinfunction "15_15") (pintype "passive"))
      (node (ref "RN18") (pin "3") (pinfunction "3_3") (pintype "passive"))
    )
    (net (code "77") (name "/IC5_GPB3") (class "Default")
      (node (ref "IC5") (pin "4") (pinfunction "GPB3_4") (pintype "bidirectional"))
      (node (ref "J5") (pin "16") (pinfunction "16_16") (pintype "passive"))
      (node (ref "RN17") (pin "3") (pinfunction "3_3") (pintype "passive"))
    )
    (net (code "78") (name "/IC5_GPB4") (class "Default")
      (node (ref "IC5") (pin "5") (pinfunction "GPB4_5") (pintype "bidirectional"))
      (node (ref "J5") (pin "17") (pinfunction "17_17") (pintype "passive"))
      (node (ref "RN18") (pin "4") (pinfunction "4_4") (pintype "passive"))
    )
    (net (code "79") (name "/IC5_GPB5") (class "Default")
      (node (ref "IC5") (pin "6") (pinfunction "GPB5_6") (pintype "bidirectional"))
      (node (ref "J5") (pin "18") (pinfunction "18_18") (pintype "passive"))
      (node (ref "RN17") (pin "4") (pinfunction "4_4") (pintype "passive"))
    )
    (net (code "80") (name "/IC5_GPB6") (class "Default")
      (node (ref "IC5") (pin "7") (pinfunction "GPB6_7") (pintype "bidirectional"))
      (node (ref "J5") (pin "19") (pinfunction "19_19") (pintype "passive"))
      (node (ref "RN18") (pin "5") (pinfunction "5_5") (pintype "passive"))
    )
    (net (code "81") (name "/IC5_GPB7") (class "Default")
      (node (ref "IC5") (pin "8") (pinfunction "GPB7_8") (pintype "bidirectional"))
      (node (ref "J5") (pin "20") (pinfunction "20_20") (pintype "passive"))
      (node (ref "RN17") (pin "5") (pinfunction "5_5") (pintype "passive"))
    )
    (net (code "82") (name "/IC6_GPA0") (class "Default")
      (node (ref "IC6") (pin "21") (pinfunction "GPA0_21") (pintype "bidirectional"))
      (node (ref "J6") (pin "10") (pinfunction "10_10") (pintype "passive"))
      (node (ref "RN23") (pin "5") (pinfunction "5_5") (pintype "passive"))
    )
    (net (code "83") (name "/IC6_GPA1") (class "Default")
      (node (ref "IC6") (pin "22") (pinfunction "GPA1_22") (pintype "bidirectional"))
      (node (ref "J6") (pin "9") (pinfunction "9_9") (pintype "passive"))
      (node (ref "RN24") (pin "5") (pinfunction "5_5") (pintype "passive"))
    )
    (net (code "84") (name "/IC6_GPA2") (class "Default")
      (node (ref "IC6") (pin "23") (pinfunction "GPA2_23") (pintype "bidirectional"))
      (node (ref "J6") (pin "8") (pinfunction "8_8") (pintype "passive"))
      (node (ref "RN23") (pin "4") (pinfunction "4_4") (pintype "passive"))
    )
    (net (code "85") (name "/IC6_GPA3") (class "Default")
      (node (ref "IC6") (pin "24") (pinfunction "GPA3_24") (pintype "bidirectional"))
      (node (ref "J6") (pin "7") (pinfunction "7_7") (pintype "passive"))
      (node (ref "RN24") (pin "4") (pinfunction "4_4") (pintype "passive"))
    )
    (net (code "86") (name "/IC6_GPA4") (class "Default")
      (node (ref "IC6") (pin "25") (pinfunction "GPA4_25") (pintype "bidirectional"))
      (node (ref "J6") (pin "3") (pinfunction "3_3") (pintype "passive"))
      (node (ref "RN24") (pin "2") (pinfunction "2_2") (pintype "passive"))
    )
    (net (code "87") (name "/IC6_GPA5") (class "Default")
      (node (ref "IC6") (pin "26") (pinfunction "GPA5_26") (pintype "bidirectional"))
      (node (ref "J6") (pin "4") (pinfunction "4_4") (pintype "passive"))
      (node (ref "RN23") (pin "2") (pinfunction "2_2") (pintype "passive"))
    )
    (net (code "88") (name "/IC6_GPA6") (class "Default")
      (node (ref "IC6") (pin "27") (pinfunction "GPA6_27") (pintype "bidirectional"))
      (node (ref "J6") (pin "5") (pinfunction "5_5") (pintype "passive"))
      (node (ref "RN24") (pin "3") (pinfunction "3_3") (pintype "passive"))
    )
    (net (code "89") (name "/IC6_GPA7") (class "Default")
      (node (ref "IC6") (pin "28") (pinfunction "GPA7_28") (pintype "bidirectional"))
      (node (ref "J6") (pin "6") (pinfunction "6_6") (pintype "passive"))
      (node (ref "RN23") (pin "3") (pinfunction "3_3") (pintype "passive"))
    )
    (net (code "90") (name "/IC6_GPB0") (class "Default")
      (node (ref "IC6") (pin "1") (pinfunction "GPB0_1") (pintype "bidirectional"))
      (node (ref "J6") (pin "13") (pinfunction "13_13") (pintype "passive"))
      (node (ref "RN22") (pin "2") (pinfunction "2_2") (pintype "passive"))
    )
    (net (code "91") (name "/IC6_GPB1") (class "Default")
      (node (ref "IC6") (pin "2") (pinfunction "GPB1_2") (pintype "bidirectional"))
      (node (ref "J6") (pin "14") (pinfunction "14_14") (pintype "passive"))
      (node (ref "RN21") (pin "2") (pinfunction "2_2") (pintype "passive"))
    )
    (net (code "92") (name "/IC6_GPB2") (class "Default")
      (node (ref "IC6") (pin "3") (pinfunction "GPB2_3") (pintype "bidirectional"))
      (node (ref "J6") (pin "15") (pinfunction "15_15") (pintype "passive"))
      (node (ref "RN22") (pin "3") (pinfunction "3_3") (pintype "passive"))
    )
    (net (code "93") (name "/IC6_GPB3") (class "Default")
      (node (ref "IC6") (pin "4") (pinfunction "GPB3_4") (pintype "bidirectional"))
      (node (ref "J6") (pin "16") (pinfunction "16_16") (pintype "passive"))
      (node (ref "RN21") (pin "3") (pinfunction "3_3") (pintype "passive"))
    )
    (net (code "94") (name "/IC6_GPB4") (class "Default")
      (node (ref "IC6") (pin "5") (pinfunction "GPB4_5") (pintype "bidirectional"))
      (node (ref "J6") (pin "17") (pinfunction "17_17") (pintype "passive"))
      (node (ref "RN22") (pin "4") (pinfunction "4_4") (pintype "passive"))
    )
    (net (code "95") (name "/IC6_GPB5") (class "Default")
      (node (ref "IC6") (pin "6") (pinfunction "GPB5_6") (pintype "bidirectional"))
      (node (ref "J6") (pin "18") (pinfunction "18_18") (pintype "passive"))
      (node (ref "RN21") (pin "4") (pinfunction "4_4") (pintype "passive"))
    )
    (net (code "96") (name "/IC6_GPB6") (class "Default")
      (node (ref "IC6") (pin "7") (pinfunction "GPB6_7") (pintype "bidirectional"))
      (node (ref "J6") (pin "19") (pinfunction "19_19") (pintype "passive"))
      (node (ref "RN22") (pin "5") (pinfunction "5_5") (pintype "passive"))
    )
    (net (code "97") (name "/IC6_GPB7") (class "Default")
      (node (ref "IC6") (pin "8") (pinfunction "GPB7_8") (pintype "bidirectional"))
      (node (ref "J6") (pin "20") (pinfunction "20_20") (pintype "passive"))
      (node (ref "RN21") (pin "5") (pinfunction "5_5") (pintype "passive"))
    )
    (net (code "98") (name "/IC7_GPA0") (class "Default")
      (node (ref "IC7") (pin "21") (pinfunction "GPA0_21") (pintype "bidirectional"))
      (node (ref "J7") (pin "10") (pinfunction "10_10") (pintype "passive"))
      (node (ref "RN27") (pin "5") (pinfunction "5_5") (pintype "passive"))
    )
    (net (code "99") (name "/IC7_GPA1") (class "Default")
      (node (ref "IC7") (pin "22") (pinfunction "GPA1_22") (pintype "bidirectional"))
      (node (ref "J7") (pin "9") (pinfunction "9_9") (pintype "passive"))
      (node (ref "RN28") (pin "5") (pinfunction "5_5") (pintype "passive"))
    )
    (net (code "100") (name "/IC7_GPA2") (class "Default")
      (node (ref "IC7") (pin "23") (pinfunction "GPA2_23") (pintype "bidirectional"))
      (node (ref "J7") (pin "8") (pinfunction "8_8") (pintype "passive"))
      (node (ref "RN27") (pin "4") (pinfunction "4_4") (pintype "passive"))
    )
    (net (code "101") (name "/IC7_GPA3") (class "Default")
      (node (ref "IC7") (pin "24") (pinfunction "GPA3_24") (pintype "bidirectional"))
      (node (ref "J7") (pin "7") (pinfunction "7_7") (pintype "passive"))
      (node (ref "RN28") (pin "4") (pinfunction "4_4") (pintype "passive"))
    )
    (net (code "102") (name "/IC7_GPA4") (class "Default")
      (node (ref "IC7") (pin "25") (pinfunction "GPA4_25") (pintype "bidirectional"))
      (node (ref "J7") (pin "3") (pinfunction "3_3") (pintype "passive"))
      (node (ref "RN28") (pin "2") (pinfunction "2_2") (pintype "passive"))
    )
    (net (code "103") (name "/IC7_GPA5") (class "Default")
      (node (ref "IC7") (pin "26") (pinfunction "GPA5_26") (pintype "bidirectional"))
      (node (ref "J7") (pin "4") (pinfunction "4_4") (pintype "passive"))
      (node (ref "RN27") (pin "2") (pinfunction "2_2") (pintype "passive"))
    )
    (net (code "104") (name "/IC7_GPA6") (class "Default")
      (node (ref "IC7") (pin "27") (pinfunction "GPA6_27") (pintype "bidirectional"))
      (node (ref "J7") (pin "5") (pinfunction "5_5") (pintype "passive"))
      (node (ref "RN28") (pin "3") (pinfunction "3_3") (pintype "passive"))
    )
    (net (code "105") (name "/IC7_GPA7") (class "Default")
      (node (ref "IC7") (pin "28") (pinfunction "GPA7_28") (pintype "bidirectional"))
      (node (ref "J7") (pin "6") (pinfunction "6_6") (pintype "passive"))
      (node (ref "RN27") (pin "3") (pinfunction "3_3") (pintype "passive"))
    )
    (net (code "106") (name "/IC7_GPB0") (class "Default")
      (node (ref "IC7") (pin "1") (pinfunction "GPB0_1") (pintype "bidirectional"))
      (node (ref "J7") (pin "13") (pinfunction "13_13") (pintype "passive"))
      (node (ref "RN26") (pin "2") (pinfunction "2_2") (pintype "passive"))
    )
    (net (code "107") (name "/IC7_GPB1") (class "Default")
      (node (ref "IC7") (pin "2") (pinfunction "GPB1_2") (pintype "bidirectional"))
      (node (ref "J7") (pin "14") (pinfunction "14_14") (pintype "passive"))
      (node (ref "RN25") (pin "2") (pinfunction "2_2") (pintype "passive"))
    )
    (net (code "108") (name "/IC7_GPB2") (class "Default")
      (node (ref "IC7") (pin "3") (pinfunction "GPB2_3") (pintype "bidirectional"))
      (node (ref "J7") (pin "15") (pinfunction "15_15") (pintype "passive"))
      (node (ref "RN26") (pin "3") (pinfunction "3_3") (pintype "passive"))
    )
    (net (code "109") (name "/IC7_GPB3") (class "Default")
      (node (ref "IC7") (pin "4") (pinfunction "GPB3_4") (pintype "bidirectional"))
      (node (ref "J7") (pin "16") (pinfunction "16_16") (pintype "passive"))
      (node (ref "RN25") (pin "3") (pinfunction "3_3") (pintype "passive"))
    )
    (net (code "110") (name "/IC7_GPB4") (class "Default")
      (node (ref "IC7") (pin "5") (pinfunction "GPB4_5") (pintype "bidirectional"))
      (node (ref "J7") (pin "17") (pinfunction "17_17") (pintype "passive"))
      (node (ref "RN26") (pin "4") (pinfunction "4_4") (pintype "passive"))
    )
    (net (code "111") (name "/IC7_GPB5") (class "Default")
      (node (ref "IC7") (pin "6") (pinfunction "GPB5_6") (pintype "bidirectional"))
      (node (ref "J7") (pin "18") (pinfunction "18_18") (pintype "passive"))
      (node (ref "RN25") (pin "4") (pinfunction "4_4") (pintype "passive"))
    )
    (net (code "112") (name "/IC7_GPB6") (class "Default")
      (node (ref "IC7") (pin "7") (pinfunction "GPB6_7") (pintype "bidirectional"))
      (node (ref "J7") (pin "19") (pinfunction "19_19") (pintype "passive"))
      (node (ref "RN26") (pin "5") (pinfunction "5_5") (pintype "passive"))
    )
    (net (code "113") (name "/IC7_GPB7") (class "Default")
      (node (ref "IC7") (pin "8") (pinfunction "GPB7_8") (pintype "bidirectional"))
      (node (ref "J7") (pin "20") (pinfunction "20_20") (pintype "passive"))
      (node (ref "RN25") (pin "5") (pinfunction "5_5") (pintype "passive"))
    )
    (net (code "114") (name "/IC8_GPA0") (class "Default")
      (node (ref "IC8") (pin "21") (pinfunction "GPA0_21") (pintype "bidirectional"))
      (node (ref "J8") (pin "10") (pinfunction "10_10") (pintype "passive"))
      (node (ref "RN31") (pin "5") (pinfunction "5_5") (pintype "passive"))
    )
    (net (code "115") (name "/IC8_GPA1") (class "Default")
      (node (ref "IC8") (pin "22") (pinfunction "GPA1_22") (pintype "bidirectional"))
      (node (ref "J8") (pin "9") (pinfunction "9_9") (pintype "passive"))
      (node (ref "RN32") (pin "5") (pinfunction "5_5") (pintype "passive"))
    )
    (net (code "116") (name "/IC8_GPA2") (class "Default")
      (node (ref "IC8") (pin "23") (pinfunction "GPA2_23") (pintype "bidirectional"))
      (node (ref "J8") (pin "8") (pinfunction "8_8") (pintype "passive"))
      (node (ref "RN31") (pin "4") (pinfunction "4_4") (pintype "passive"))
    )
    (net (code "117") (name "/IC8_GPA3") (class "Default")
      (node (ref "IC8") (pin "24") (pinfunction "GPA3_24") (pintype "bidirectional"))
      (node (ref "J8") (pin "7") (pinfunction "7_7") (pintype "passive"))
      (node (ref "RN32") (pin "4") (pinfunction "4_4") (pintype "passive"))
    )
    (net (code "118") (name "/IC8_GPA4") (class "Default")
      (node (ref "IC8") (pin "25") (pinfunction "GPA4_25") (pintype "bidirectional"))
      (node (ref "J8") (pin "3") (pinfunction "3_3") (pintype "passive"))
      (node (ref "RN32") (pin "2") (pinfunction "2_2") (pintype "passive"))
    )
    (net (code "119") (name "/IC8_GPA5") (class "Default")
      (node (ref "IC8") (pin "26") (pinfunction "GPA5_26") (pintype "bidirectional"))
      (node (ref "J8") (pin "4") (pinfunction "4_4") (pintype "passive"))
      (node (ref "RN31") (pin "2") (pinfunction "2_2") (pintype "passive"))
    )
    (net (code "120") (name "/IC8_GPA6") (class "Default")
      (node (ref "IC8") (pin "27") (pinfunction "GPA6_27") (pintype "bidirectional"))
      (node (ref "J8") (pin "5") (pinfunction "5_5") (pintype "passive"))
      (node (ref "RN32") (pin "3") (pinfunction "3_3") (pintype "passive"))
    )
    (net (code "121") (name "/IC8_GPA7") (class "Default")
      (node (ref "IC8") (pin "28") (pinfunction "GPA7_28") (pintype "bidirectional"))
      (node (ref "J8") (pin "6") (pinfunction "6_6") (pintype "passive"))
      (node (ref "RN31") (pin "3") (pinfunction "3_3") (pintype "passive"))
    )
    (net (code "122") (name "/IC8_GPB0") (class "Default")
      (node (ref "IC8") (pin "1") (pinfunction "GPB0_1") (pintype "bidirectional"))
      (node (ref "J8") (pin "13") (pinfunction "13_13") (pintype "passive"))
      (node (ref "RN30") (pin "2") (pinfunction "2_2") (pintype "passive"))
    )
    (net (code "123") (name "/IC8_GPB1") (class "Default")
      (node (ref "IC8") (pin "2") (pinfunction "GPB1_2") (pintype "bidirectional"))
      (node (ref "J8") (pin "14") (pinfunction "14_14") (pintype "passive"))
      (node (ref "RN29") (pin "2") (pinfunction "2_2") (pintype "passive"))
    )
    (net (code "124") (name "/IC8_GPB2") (class "Default")
      (node (ref "IC8") (pin "3") (pinfunction "GPB2_3") (pintype "bidirectional"))
      (node (ref "J8") (pin "15") (pinfunction "15_15") (pintype "passive"))
      (node (ref "RN30") (pin "3") (pinfunction "3_3") (pintype "passive"))
    )
    (net (code "125") (name "/IC8_GPB3") (class "Default")
      (node (ref "IC8") (pin "4") (pinfunction "GPB3_4") (pintype "bidirectional"))
      (node (ref "J8") (pin "16") (pinfunction "16_16") (pintype "passive"))
      (node (ref "RN29") (pin "3") (pinfunction "3_3") (pintype "passive"))
    )
    (net (code "126") (name "/IC8_GPB4") (class "Default")
      (node (ref "IC8") (pin "5") (pinfunction "GPB4_5") (pintype "bidirectional"))
      (node (ref "J8") (pin "17") (pinfunction "17_17") (pintype "passive"))
      (node (ref "RN30") (pin "4") (pinfunction "4_4") (pintype "passive"))
    )
    (net (code "127") (name "/IC8_GPB5") (class "Default")
      (node (ref "IC8") (pin "6") (pinfunction "GPB5_6") (pintype "bidirectional"))
      (node (ref "J8") (pin "18") (pinfunction "18_18") (pintype "passive"))
      (node (ref "RN29") (pin "4") (pinfunction "4_4") (pintype "passive"))
    )
    (net (code "128") (name "/IC8_GPB6") (class "Default")
      (node (ref "IC8") (pin "7") (pinfunction "GPB6_7") (pintype "bidirectional"))
      (node (ref "J8") (pin "19") (pinfunction "19_19") (pintype "passive"))
      (node (ref "RN30") (pin "5") (pinfunction "5_5") (pintype "passive"))
    )
    (net (code "129") (name "/IC8_GPB7") (class "Default")
      (node (ref "IC8") (pin "8") (pinfunction "GPB7_8") (pintype "bidirectional"))
      (node (ref "J8") (pin "20") (pinfunction "20_20") (pintype "passive"))
      (node (ref "RN29") (pin "5") (pinfunction "5_5") (pintype "passive"))
    )
    (net (code "130") (name "/MOUT") (class "Default")
      (node (ref "D23") (pin "A") (pinfunction "A_A") (pintype "passive"))
      (node (ref "D24") (pin "C") (pinfunction "C_C") (pintype "passive"))
      (node (ref "IC10") (pin "4") (pinfunction "O_4") (pintype "tri_state"))
      (node (ref "R13") (pin "2") (pinfunction "2_2") (pintype "passive"))
    )
    (net (code "131") (name "3.3V") (class "Default")
      (node (ref "C1") (pin "1") (pinfunction "1_1") (pintype "passive"))
      (node (ref "C2") (pin "1") (pinfunction "1_1") (pintype "passive"))
      (node (ref "C29") (pin "2") (pinfunction "2_2") (pintype "passive"))
      (node (ref "C3") (pin "1") (pinfunction "1_1") (pintype "passive"))
      (node (ref "C4") (pin "1") (pinfunction "1_1") (pintype "passive"))
      (node (ref "C5") (pin "1") (pinfunction "1_1") (pintype "passive"))
      (node (ref "C6") (pin "1") (pinfunction "1_1") (pintype "passive"))
      (node (ref "C7") (pin "1") (pinfunction "1_1") (pintype "passive"))
      (node (ref "C8") (pin "1") (pinfunction "1_1") (pintype "passive"))
      (node (ref "C9") (pin "2") (pinfunction "2_2") (pintype "passive"))
      (node (ref "D18") (pin "C") (pinfunction "C_C") (pintype "passive"))
      (node (ref "IC1") (pin "9") (pinfunction "VDD_9") (pintype "power_in"))
      (node (ref "IC12") (pin "2") (pinfunction "VOUT_2") (pintype "power_in"))
      (node (ref "IC12") (pin "4") (pinfunction "VOUT_4") (pintype "power_in"))
      (node (ref "IC2") (pin "9") (pinfunction "VDD_9") (pintype "power_in"))
      (node (ref "IC3") (pin "9") (pinfunction "VDD_9") (pintype "power_in"))
      (node (ref "IC4") (pin "9") (pinfunction "VDD_9") (pintype "power_in"))
      (node (ref "IC5") (pin "9") (pinfunction "VDD_9") (pintype "power_in"))
      (node (ref "IC6") (pin "9") (pinfunction "VDD_9") (pintype "power_in"))
      (node (ref "IC7") (pin "9") (pinfunction "VDD_9") (pintype "power_in"))
      (node (ref "IC8") (pin "9") (pinfunction "VDD_9") (pintype "power_in"))
      (node (ref "IC9") (pin "J2.2") (pinfunction "VIN1_J2.2") (pintype "power_in"))
      (node (ref "IC9") (pin "J2.3") (pinfunction "VIN2_J2.3") (pintype "power_in"))
      (node (ref "OC1") (pin "6") (pinfunction "VCC_6") (pintype "power_in"))
      (node (ref "R1") (pin "1") (pinfunction "1_1") (pintype "passive"))
      (node (ref "R11") (pin "2") (pinfunction "2_2") (pintype "passive"))
      (node (ref "R16") (pin "2") (pinfunction "2_2") (pintype "passive"))
      (node (ref "R2") (pin "2") (pinfunction "2_2") (pintype "passive"))
      (node (ref "R3") (pin "2") (pinfunction "2_2") (pintype "passive"))
      (node (ref "R4") (pin "2") (pinfunction "2_2") (pintype "passive"))
      (node (ref "R5") (pin "2") (pinfunction "2_2") (pintype "passive"))
      (node (ref "R56") (pin "2") (pinfunction "2_2") (pintype "passive"))
      (node (ref "R58") (pin "2") (pinfunction "2_2") (pintype "passive"))
      (node (ref "R6") (pin "2") (pinfunction "2_2") (pintype "passive"))
      (node (ref "R7") (pin "2") (pinfunction "2_2") (pintype "passive"))
      (node (ref "R8") (pin "2") (pinfunction "2_2") (pintype "passive"))
      (node (ref "R9") (pin "1") (pinfunction "1_1") (pintype "passive"))
      (node (ref "RN1") (pin "1") (pinfunction "1_1") (pintype "passive"))
      (node (ref "RN10") (pin "1") (pinfunction "1_1") (pintype "passive"))
      (node (ref "RN11") (pin "1") (pinfunction "1_1") (pintype "passive"))
      (node (ref "RN12") (pin "1") (pinfunction "1_1") (pintype "passive"))
      (node (ref "RN13") (pin "1") (pinfunction "1_1") (pintype "passive"))
      (node (ref "RN14") (pin "1") (pinfunction "1_1") (pintype "passive"))
      (node (ref "RN15") (pin "1") (pinfunction "1_1") (pintype "passive"))
      (node (ref "RN16") (pin "1") (pinfunction "1_1") (pintype "passive"))
      (node (ref "RN17") (pin "1") (pinfunction "1_1") (pintype "passive"))
      (node (ref "RN18") (pin "1") (pinfunction "1_1") (pintype "passive"))
      (node (ref "RN19") (pin "1") (pinfunction "1_1") (pintype "passive"))
      (node (ref "RN2") (pin "1") (pinfunction "1_1") (pintype "passive"))
      (node (ref "RN20") (pin "1") (pinfunction "1_1") (pintype "passive"))
      (node (ref "RN21") (pin "1") (pinfunction "1_1") (pintype "passive"))
      (node (ref "RN22") (pin "1") (pinfunction "1_1") (pintype "passive"))
      (node (ref "RN23") (pin "1") (pinfunction "1_1") (pintype "passive"))
      (node (ref "RN24") (pin "1") (pinfunction "1_1") (pintype "passive"))
      (node (ref "RN25") (pin "1") (pinfunction "1_1") (pintype "passive"))
      (node (ref "RN26") (pin "1") (pinfunction "1_1") (pintype "passive"))
      (node (ref "RN27") (pin "1") (pinfunction "1_1") (pintype "passive"))
      (node (ref "RN28") (pin "1") (pinfunction "1_1") (pintype "passive"))
      (node (ref "RN29") (pin "1") (pinfunction "1_1") (pintype "passive"))
      (node (ref "RN3") (pin "1") (pinfunction "1_1") (pintype "passive"))
      (node (ref "RN30") (pin "1") (pinfunction "1_1") (pintype "passive"))
      (node (ref "RN31") (pin "1") (pinfunction "1_1") (pintype "passive"))
      (node (ref "RN32") (pin "1") (pinfunction "1_1") (pintype "passive"))
      (node (ref "RN4") (pin "1") (pinfunction "1_1") (pintype "passive"))
      (node (ref "RN5") (pin "1") (pinfunction "1_1") (pintype "passive"))
      (node (ref "RN6") (pin "1") (pinfunction "1_1") (pintype "passive"))
      (node (ref "RN7") (pin "1") (pinfunction "1_1") (pintype "passive"))
      (node (ref "RN8") (pin "1") (pinfunction "1_1") (pintype "passive"))
      (node (ref "RN9") (pin "1") (pinfunction "1_1") (pintype "passive"))
    )
    (net (code "132") (name "5V") (class "Default")
      (node (ref "C24") (pin "2") (pinfunction "2_2") (pintype "passive"))
      (node (ref "C28") (pin "2") (pinfunction "2_2") (pintype "passive"))
      (node (ref "D1") (pin "C") (pinfunction "C_C") (pintype "passive"))
      (node (ref "D19") (pin "C") (pinfunction "C_C") (pintype "passive"))
      (node (ref "D23") (pin "C") (pinfunction "C_C") (pintype "passive"))
      (node (ref "IC10") (pin "5") (pinfunction "VCC_5") (pintype "power_in"))
      (node (ref "IC11") (pin "3") (pinfunction "VOUT_3") (pintype "power_in"))
      (node (ref "IC12") (pin "3") (pinfunction "VIN_3") (pintype "power_in"))
      (node (ref "R12") (pin "2") (pinfunction "2_2") (pintype "passive"))
      (node (ref "R14") (pin "2") (pinfunction "2_2") (pintype "passive"))
      (node (ref "U$1") (pin "VIN") (pinfunction "VIN(3.6-6V)_VIN") (pintype "power_in"))
    )
    (net (code "133") (name "D0{slash}RXI1") (class "Default")
      (node (ref "IC10") (pin "2") (pinfunction "I_2") (pintype "input"))
      (node (ref "OC1") (pin "4") (pinfunction "OUT_4") (pintype "bidirectional"))
      (node (ref "R11") (pin "1") (pinfunction "1_1") (pintype "passive"))
      (node (ref "R58") (pin "1") (pinfunction "1_1") (pintype "passive"))
      (node (ref "U$1") (pin "0") (pinfunction "D0/TOUCH/MOSI1/RX1_0") (pintype "bidirectional"))
    )
    (net (code "134") (name "D1{slash}TXO") (class "Default")
      (node (ref "D1") (pin "A") (pinfunction "A_A") (pintype "passive"))
      (node (ref "D3") (pin "C") (pinfunction "C_C") (pintype "passive"))
      (node (ref "R15") (pin "2") (pinfunction "2_2") (pintype "passive"))
      (node (ref "U$1") (pin "1") (pinfunction "D1/TOUCH/MISO1/TX1_1") (pintype "bidirectional"))
    )
    (net (code "135") (name "DEBUG_LED") (class "Default")
      (node (ref "DEBUG") (pin "C") (pinfunction "C_C") (pintype "passive"))
      (node (ref "U$1") (pin "16") (pinfunction "D16/A2/TOUCH/(SCL0)_16") (pintype "bidirectional"))
    )
    (net (code "136") (name "ETH_INT") (class "Default")
      (node (ref "IC9") (pin "J1.6") (pinfunction "/INT_J1.6") (pintype "output"))
      (node (ref "U$1") (pin "9") (pinfunction "D9/CS0/RX2/PWM_9") (pintype "bidirectional"))
    )
    (net (code "137") (name "ETH_MISO") (class "Default")
      (node (ref "IC9") (pin "J2.6") (pinfunction "MISO_J2.6") (pintype "output"))
      (node (ref "U$1") (pin "12") (pinfunction "D12/MISO0_12") (pintype "bidirectional"))
    )
    (net (code "138") (name "ETH_MOSI") (class "Default")
      (node (ref "IC9") (pin "J1.3") (pinfunction "MOSI_J1.3") (pintype "input"))
      (node (ref "U$1") (pin "11") (pinfunction "D11/MOSI0_11") (pintype "bidirectional"))
    )
    (net (code "139") (name "ETH_RST") (class "Default")
      (node (ref "IC9") (pin "J2.5") (pinfunction "/RESET_J2.5") (pintype "input"))
      (node (ref "U$1") (pin "39") (pinfunction "D39/A20_39") (pintype "bidirectional"))
    )
    (net (code "140") (name "ETH_SCLK") (class "Default")
      (node (ref "IC9") (pin "J1.4") (pinfunction "SCLK_J1.4") (pintype "input"))
      (node (ref "U$1") (pin "13") (pinfunction "D13/LED/SCK0_13") (pintype "bidirectional"))
    )
    (net (code "141") (name "ETH_SS") (class "Default")
      (node (ref "IC9") (pin "J1.5") (pinfunction "/SS_J1.5") (pintype "input"))
      (node (ref "U$1") (pin "10") (pinfunction "D10/CS0/TX2/PWM_10") (pintype "bidirectional"))
    )
    (net (code "142") (name "GND") (class "Default")
      (node (ref "C1") (pin "2") (pinfunction "2_2") (pintype "passive"))
      (node (ref "C18") (pin "1") (pinfunction "1_1") (pintype "passive"))
      (node (ref "C2") (pin "2") (pinfunction "2_2") (pintype "passive"))
      (node (ref "C24") (pin "1") (pinfunction "1_1") (pintype "passive"))
      (node (ref "C28") (pin "1") (pinfunction "1_1") (pintype "passive"))
      (node (ref "C29") (pin "1") (pinfunction "1_1") (pintype "passive"))
      (node (ref "C3") (pin "2") (pinfunction "2_2") (pintype "passive"))
      (node (ref "C4") (pin "2") (pinfunction "2_2") (pintype "passive"))
      (node (ref "C5") (pin "2") (pinfunction "2_2") (pintype "passive"))
      (node (ref "C6") (pin "2") (pinfunction "2_2") (pintype "passive"))
      (node (ref "C7") (pin "2") (pinfunction "2_2") (pintype "passive"))
      (node (ref "C8") (pin "2") (pinfunction "2_2") (pintype "passive"))
      (node (ref "C9") (pin "1") (pinfunction "1_1") (pintype "passive"))
      (node (ref "D18") (pin "A") (pinfunction "A_A") (pintype "passive"))
      (node (ref "D19") (pin "A") (pinfunction "A_A") (pintype "passive"))
      (node (ref "D24") (pin "A") (pinfunction "A_A") (pintype "passive"))
      (node (ref "D3") (pin "A") (pinfunction "A_A") (pintype "passive"))
      (node (ref "IC1") (pin "10") (pinfunction "VSS_10") (pintype "power_in"))
      (node (ref "IC1") (pin "15") (pinfunction "A0_15") (pintype "input"))
      (node (ref "IC1") (pin "16") (pinfunction "A1_16") (pintype "input"))
      (node (ref "IC1") (pin "17") (pinfunction "A2_17") (pintype "input"))
      (node (ref "IC10") (pin "1") (pinfunction "OE_1") (pintype "input"))
      (node (ref "IC10") (pin "3") (pinfunction "GND_3") (pintype "power_in"))
      (node (ref "IC11") (pin "2") (pinfunction "GND_2") (pintype "power_in"))
      (node (ref "IC12") (pin "1") (pinfunction "GND_1") (pintype "power_in"))
      (node (ref "IC2") (pin "10") (pinfunction "VSS_10") (pintype "power_in"))
      (node (ref "IC2") (pin "16") (pinfunction "A1_16") (pintype "input"))
      (node (ref "IC2") (pin "17") (pinfunction "A2_17") (pintype "input"))
      (node (ref "IC3") (pin "10") (pinfunction "VSS_10") (pintype "power_in"))
      (node (ref "IC3") (pin "15") (pinfunction "A0_15") (pintype "input"))
      (node (ref "IC3") (pin "17") (pinfunction "A2_17") (pintype "input"))
      (node (ref "IC4") (pin "10") (pinfunction "VSS_10") (pintype "power_in"))
      (node (ref "IC4") (pin "17") (pinfunction "A2_17") (pintype "input"))
      (node (ref "IC5") (pin "10") (pinfunction "VSS_10") (pintype "power_in"))
      (node (ref "IC5") (pin "15") (pinfunction "A0_15") (pintype "input"))
      (node (ref "IC5") (pin "16") (pinfunction "A1_16") (pintype "input"))
      (node (ref "IC6") (pin "10") (pinfunction "VSS_10") (pintype "power_in"))
      (node (ref "IC6") (pin "16") (pinfunction "A1_16") (pintype "input"))
      (node (ref "IC7") (pin "10") (pinfunction "VSS_10") (pintype "power_in"))
      (node (ref "IC7") (pin "15") (pinfunction "A0_15") (pintype "input"))
      (node (ref "IC8") (pin "10") (pinfunction "VSS_10") (pintype "power_in"))
      (node (ref "IC9") (pin "J1.1") (pinfunction "GND1_J1.1") (pintype "power_in"))
      (node (ref "IC9") (pin "J1.2") (pinfunction "GND2_J1.2") (pintype "power_in"))
      (node (ref "IC9") (pin "J2.1") (pinfunction "GND3_J2.1") (pintype "power_in"))
      (node (ref "IC9") (pin "J2.4") (pinfunction "PWDN_J2.4") (pintype "input"))
      (node (ref "J1") (pin "1") (pinfunction "1_1") (pintype "passive"))
      (node (ref "J1") (pin "11") (pinfunction "11_11") (pintype "passive"))
      (node (ref "J1") (pin "12") (pinfunction "12_12") (pintype "passive"))
      (node (ref "J1") (pin "2") (pinfunction "2_2") (pintype "passive"))
      (node (ref "J12") (pin "2") (pinfunction "2_2") (pintype "bidirectional"))
      (node (ref "J2") (pin "1") (pinfunction "1_1") (pintype "passive"))
      (node (ref "J2") (pin "11") (pinfunction "11_11") (pintype "passive"))
      (node (ref "J2") (pin "12") (pinfunction "12_12") (pintype "passive"))
      (node (ref "J2") (pin "2") (pinfunction "2_2") (pintype "passive"))
      (node (ref "J3") (pin "1") (pinfunction "1_1") (pintype "passive"))
      (node (ref "J3") (pin "11") (pinfunction "11_11") (pintype "passive"))
      (node (ref "J3") (pin "12") (pinfunction "12_12") (pintype "passive"))
      (node (ref "J3") (pin "2") (pinfunction "2_2") (pintype "passive"))
      (node (ref "J4") (pin "1") (pinfunction "1_1") (pintype "passive"))
      (node (ref "J4") (pin "11") (pinfunction "11_11") (pintype "passive"))
      (node (ref "J4") (pin "12") (pinfunction "12_12") (pintype "passive"))
      (node (ref "J4") (pin "2") (pinfunction "2_2") (pintype "passive"))
      (node (ref "J5") (pin "1") (pinfunction "1_1") (pintype "passive"))
      (node (ref "J5") (pin "11") (pinfunction "11_11") (pintype "passive"))
      (node (ref "J5") (pin "12") (pinfunction "12_12") (pintype "passive"))
      (node (ref "J5") (pin "2") (pinfunction "2_2") (pintype "passive"))
      (node (ref "J6") (pin "1") (pinfunction "1_1") (pintype "passive"))
      (node (ref "J6") (pin "11") (pinfunction "11_11") (pintype "passive"))
      (node (ref "J6") (pin "12") (pinfunction "12_12") (pintype "passive"))
      (node (ref "J6") (pin "2") (pinfunction "2_2") (pintype "passive"))
      (node (ref "J7") (pin "1") (pinfunction "1_1") (pintype "passive"))
      (node (ref "J7") (pin "11") (pinfunction "11_11") (pintype "passive"))
      (node (ref "J7") (pin "12") (pinfunction "12_12") (pintype "passive"))
      (node (ref "J7") (pin "2") (pinfunction "2_2") (pintype "passive"))
      (node (ref "J8") (pin "1") (pinfunction "1_1") (pintype "passive"))
      (node (ref "J8") (pin "11") (pinfunction "11_11") (pintype "passive"))
      (node (ref "J8") (pin "12") (pinfunction "12_12") (pintype "passive"))
      (node (ref "J8") (pin "2") (pinfunction "2_2") (pintype "passive"))
      (node (ref "OC1") (pin "5") (pinfunction "GND_5") (pintype "power_in"))
      (node (ref "ON") (pin "C") (pinfunction "C_C") (pintype "passive"))
      (node (ref "OUT") (pin "3") (pinfunction "3_3") (pintype "passive"))
      (node (ref "R17") (pin "2") (pinfunction "2_2") (pintype "passive"))
      (node (ref "R26") (pin "2") (pinfunction "2_2") (pintype "passive"))
      (node (ref "S1") (pin "C1") (pinfunction "C1_C1") (pintype "passive"))
      (node (ref "S1") (pin "C2") (pinfunction "C2_C2") (pintype "passive"))
      (node (ref "SV1") (pin "1") (pinfunction "1_1") (pintype "passive"))
      (node (ref "SV2") (pin "1") (pinfunction "1_1") (pintype "passive"))
      (node (ref "SV25") (pin "1") (pinfunction "1_1") (pintype "passive"))
      (node (ref "THRU") (pin "3") (pinfunction "3_3") (pintype "passive"))
      (node (ref "U$1") (pin "AGND") (pinfunction "AGND_AGND") (pintype "power_in"))
      (node (ref "U$1") (pin "GND1") (pinfunction "GND_GND1") (pintype "power_in"))
      (node (ref "U$1") (pin "GND2") (pinfunction "GND_GND2") (pintype "power_in"))
    )
    (net (code "143") (name "MIDICHSW_1") (class "Default")
      (node (ref "S1") (pin "1") (pinfunction "1_1") (pintype "passive"))
      (node (ref "U$1") (pin "24") (pinfunction "D24_24") (pintype "bidirectional"))
    )
    (net (code "144") (name "MIDICHSW_2") (class "Default")
      (node (ref "S1") (pin "2") (pinfunction "2_2") (pintype "passive"))
      (node (ref "U$1") (pin "27") (pinfunction "D27/(RX1)_27") (pintype "bidirectional"))
    )
    (net (code "145") (name "MIDICHSW_4") (class "Default")
      (node (ref "S1") (pin "4") (pinfunction "4_4") (pintype "passive"))
      (node (ref "U$1") (pin "25") (pinfunction "D25_25") (pintype "bidirectional"))
    )
    (net (code "146") (name "MIDICHSW_8") (class "Default")
      (node (ref "S1") (pin "8") (pinfunction "8_8") (pintype "passive"))
      (node (ref "U$1") (pin "26") (pinfunction "D26/(TX1)_26") (pintype "bidirectional"))
    )
    (net (code "147") (name "Net-(C18-Pad2)") (class "Default")
      (node (ref "C18") (pin "2") (pinfunction "2_2") (pintype "passive"))
      (node (ref "J9") (pin "2") (pinfunction "2_2") (pintype "bidirectional"))
    )
    (net (code "148") (name "Net-(DEBUG-PadA)") (class "Default")
      (node (ref "DEBUG") (pin "A") (pinfunction "A_A") (pintype "passive"))
      (node (ref "R16") (pin "1") (pinfunction "1_1") (pintype "passive"))
    )
    (net (code "149") (name "Net-(IC1-INTA)") (class "Default")
      (node (ref "IC1") (pin "20") (pinfunction "INTA_20") (pintype "output"))
      (node (ref "SV3") (pin "2") (pinfunction "2_2") (pintype "passive"))
    )
    (net (code "150") (name "Net-(IC1-INTB)") (class "Default")
      (node (ref "IC1") (pin "19") (pinfunction "INTB_19") (pintype "output"))
      (node (ref "SV3") (pin "1") (pinfunction "1_1") (pintype "passive"))
    )
    (net (code "151") (name "Net-(IC2-A0)") (class "Default")
      (node (ref "IC2") (pin "15") (pinfunction "A0_15") (pintype "input"))
      (node (ref "R2") (pin "1") (pinfunction "1_1") (pintype "passive"))
    )
    (net (code "152") (name "Net-(IC2-INTA)") (class "Default")
      (node (ref "IC2") (pin "20") (pinfunction "INTA_20") (pintype "output"))
      (node (ref "SV6") (pin "2") (pinfunction "2_2") (pintype "passive"))
    )
    (net (code "153") (name "Net-(IC2-INTB)") (class "Default")
      (node (ref "IC2") (pin "19") (pinfunction "INTB_19") (pintype "output"))
      (node (ref "SV6") (pin "1") (pinfunction "1_1") (pintype "passive"))
    )
    (net (code "154") (name "Net-(IC3-A1)") (class "Default")
      (node (ref "IC3") (pin "16") (pinfunction "A1_16") (pintype "input"))
      (node (ref "R3") (pin "1") (pinfunction "1_1") (pintype "passive"))
    )
    (net (code "155") (name "Net-(IC3-INTA)") (class "Default")
      (node (ref "IC3") (pin "20") (pinfunction "INTA_20") (pintype "output"))
      (node (ref "SV9") (pin "2") (pinfunction "2_2") (pintype "passive"))
    )
    (net (code "156") (name "Net-(IC3-INTB)") (class "Default")
      (node (ref "IC3") (pin "19") (pinfunction "INTB_19") (pintype "output"))
      (node (ref "SV9") (pin "1") (pinfunction "1_1") (pintype "passive"))
    )
    (net (code "157") (name "Net-(IC4-A0)") (class "Default")
      (node (ref "IC4") (pin "15") (pinfunction "A0_15") (pintype "input"))
      (node (ref "IC4") (pin "16") (pinfunction "A1_16") (pintype "input"))
      (node (ref "R4") (pin "1") (pinfunction "1_1") (pintype "passive"))
    )
    (net (code "158") (name "Net-(IC4-INTA)") (class "Default")
      (node (ref "IC4") (pin "20") (pinfunction "INTA_20") (pintype "output"))
      (node (ref "SV12") (pin "2") (pinfunction "2_2") (pintype "passive"))
    )
    (net (code "159") (name "Net-(IC4-INTB)") (class "Default")
      (node (ref "IC4") (pin "19") (pinfunction "INTB_19") (pintype "output"))
      (node (ref "SV12") (pin "1") (pinfunction "1_1") (pintype "passive"))
    )
    (net (code "160") (name "Net-(IC5-A2)") (class "Default")
      (node (ref "IC5") (pin "17") (pinfunction "A2_17") (pintype "input"))
      (node (ref "R5") (pin "1") (pinfunction "1_1") (pintype "passive"))
    )
    (net (code "161") (name "Net-(IC5-INTA)") (class "Default")
      (node (ref "IC5") (pin "20") (pinfunction "INTA_20") (pintype "output"))
      (node (ref "SV15") (pin "2") (pinfunction "2_2") (pintype "passive"))
    )
    (net (code "162") (name "Net-(IC5-INTB)") (class "Default")
      (node (ref "IC5") (pin "19") (pinfunction "INTB_19") (pintype "output"))
      (node (ref "SV15") (pin "1") (pinfunction "1_1") (pintype "passive"))
    )
    (net (code "163") (name "Net-(IC6-A0)") (class "Default")
      (node (ref "IC6") (pin "15") (pinfunction "A0_15") (pintype "input"))
      (node (ref "IC6") (pin "17") (pinfunction "A2_17") (pintype "input"))
      (node (ref "R6") (pin "1") (pinfunction "1_1") (pintype "passive"))
    )
    (net (code "164") (name "Net-(IC6-INTA)") (class "Default")
      (node (ref "IC6") (pin "20") (pinfunction "INTA_20") (pintype "output"))
      (node (ref "SV18") (pin "2") (pinfunction "2_2") (pintype "passive"))
    )
    (net (code "165") (name "Net-(IC6-INTB)") (class "Default")
      (node (ref "IC6") (pin "19") (pinfunction "INTB_19") (pintype "output"))
      (node (ref "SV18") (pin "1") (pinfunction "1_1") (pintype "passive"))
    )
    (net (code "166") (name "Net-(IC7-A1)") (class "Default")
      (node (ref "IC7") (pin "16") (pinfunction "A1_16") (pintype "input"))
      (node (ref "IC7") (pin "17") (pinfunction "A2_17") (pintype "input"))
      (node (ref "R7") (pin "1") (pinfunction "1_1") (pintype "passive"))
    )
    (net (code "167") (name "Net-(IC7-INTA)") (class "Default")
      (node (ref "IC7") (pin "20") (pinfunction "INTA_20") (pintype "output"))
      (node (ref "SV21") (pin "2") (pinfunction "2_2") (pintype "passive"))
    )
    (net (code "168") (name "Net-(IC7-INTB)") (class "Default")
      (node (ref "IC7") (pin "19") (pinfunction "INTB_19") (pintype "output"))
      (node (ref "SV21") (pin "1") (pinfunction "1_1") (pintype "passive"))
    )
    (net (code "169") (name "Net-(IC8-A0)") (class "Default")
      (node (ref "IC8") (pin "15") (pinfunction "A0_15") (pintype "input"))
      (node (ref "IC8") (pin "16") (pinfunction "A1_16") (pintype "input"))
      (node (ref "IC8") (pin "17") (pinfunction "A2_17") (pintype "input"))
      (node (ref "R8") (pin "1") (pinfunction "1_1") (pintype "passive"))
    )
    (net (code "170") (name "Net-(IC8-INTA)") (class "Default")
      (node (ref "IC8") (pin "20") (pinfunction "INTA_20") (pintype "output"))
      (node (ref "SV24") (pin "2") (pinfunction "2_2") (pintype "passive"))
    )
    (net (code "171") (name "Net-(IC8-INTB)") (class "Default")
      (node (ref "IC8") (pin "19") (pinfunction "INTB_19") (pintype "output"))
      (node (ref "SV24") (pin "1") (pinfunction "1_1") (pintype "passive"))
    )
    (net (code "172") (name "Net-(IC11-VIN)") (class "Default")
      (node (ref "IC11") (pin "1") (pinfunction "VIN_1") (pintype "power_in"))
      (node (ref "U$5") (pin "P$3") (pinfunction "O_P$3") (pintype "passive"))
    )
    (net (code "173") (name "Net-(IN-Pad2)") (class "Default")
      (node (ref "IN") (pin "2") (pinfunction "2_2") (pintype "passive"))
      (node (ref "J9") (pin "4") (pinfunction "4_4") (pintype "bidirectional"))
      (node (ref "R10") (pin "1") (pinfunction "1_1") (pintype "passive"))
    )
    (net (code "174") (name "Net-(J10-Pad2)") (class "Default")
      (node (ref "J10") (pin "2") (pinfunction "2_2") (pintype "bidirectional"))
      (node (ref "R26") (pin "1") (pinfunction "1_1") (pintype "passive"))
    )
    (net (code "175") (name "Net-(J10-Pad4)") (class "Default")
      (node (ref "J10") (pin "4") (pinfunction "4_4") (pintype "bidirectional"))
      (node (ref "R12") (pin "1") (pinfunction "1_1") (pintype "passive"))
      (node (ref "THRU") (pin "2") (pinfunction "2_2") (pintype "passive"))
    )
    (net (code "176") (name "Net-(J10-Pad5)") (class "Default")
      (node (ref "J10") (pin "5") (pinfunction "5_5") (pintype "bidirectional"))
      (node (ref "R13") (pin "1") (pinfunction "1_1") (pintype "passive"))
      (node (ref "THRU") (pin "1") (pinfunction "1_1") (pintype "passive"))
    )
    (net (code "177") (name "Net-(J11-Pad2)") (class "Default")
      (node (ref "J11") (pin "2") (pinfunction "2_2") (pintype "bidirectional"))
      (node (ref "R17") (pin "1") (pinfunction "1_1") (pintype "passive"))
    )
    (net (code "178") (name "Net-(J11-Pad4)") (class "Default")
      (node (ref "J11") (pin "4") (pinfunction "4_4") (pintype "bidirectional"))
      (node (ref "OUT") (pin "2") (pinfunction "2_2") (pintype "passive"))
      (node (ref "R14") (pin "1") (pinfunction "1_1") (pintype "passive"))
    )
    (net (code "179") (name "Net-(J11-Pad5)") (class "Default")
      (node (ref "J11") (pin "5") (pinfunction "5_5") (pintype "bidirectional"))
      (node (ref "OUT") (pin "1") (pinfunction "1_1") (pintype "passive"))
      (node (ref "R15") (pin "1") (pinfunction "1_1") (pintype "passive"))
    )
    (net (code "180") (name "Net-(OC1-A)") (class "Default")
      (node (ref "D2") (pin "C") (pinfunction "C_C") (pintype "passive"))
      (node (ref "OC1") (pin "1") (pinfunction "A_1") (pintype "bidirectional"))
      (node (ref "R10") (pin "2") (pinfunction "2_2") (pintype "passive"))
    )
    (net (code "181") (name "Net-(OC1-C)") (class "Default")
      (node (ref "D2") (pin "A") (pinfunction "A_A") (pintype "passive"))
      (node (ref "IN") (pin "1") (pinfunction "1_1") (pintype "passive"))
      (node (ref "J9") (pin "5") (pinfunction "5_5") (pintype "bidirectional"))
      (node (ref "OC1") (pin "3") (pinfunction "C_3") (pintype "bidirectional"))
    )
    (net (code "182") (name "Net-(ON-PadA)") (class "Default")
      (node (ref "ON") (pin "A") (pinfunction "A_A") (pintype "passive"))
      (node (ref "R56") (pin "1") (pinfunction "1_1") (pintype "passive"))
    )
    (net (code "183") (name "Net-(U$1-D3{slash}SCL2{slash}CAN0TX{slash}PWM)") (class "Default")
      (node (ref "SV1") (pin "2") (pinfunction "2_2") (pintype "passive"))
      (node (ref "U$1") (pin "3") (pinfunction "D3/SCL2/CAN0TX/PWM_3") (pintype "bidirectional"))
    )
    (net (code "184") (name "Net-(U$1-D4{slash}SDA2{slash}CAN0RX{slash}PWM)") (class "Default")
      (node (ref "SV1") (pin "3") (pinfunction "3_3") (pintype "passive"))
      (node (ref "U$1") (pin "4") (pinfunction "D4/SDA2/CAN0RX/PWM_4") (pintype "bidirectional"))
    )
    (net (code "185") (name "Net-(U$1-D37{slash}A18{slash}SCL1{slash}PWM)") (class "Default")
      (node (ref "SV2") (pin "2") (pinfunction "2_2") (pintype "passive"))
      (node (ref "U$1") (pin "37") (pinfunction "D37/A18/SCL1/PWM_37") (pintype "bidirectional"))
    )
    (net (code "186") (name "Net-(U$1-D38{slash}A19{slash}SDA1{slash}PWM)") (class "Default")
      (node (ref "SV2") (pin "3") (pinfunction "3_3") (pintype "passive"))
      (node (ref "U$1") (pin "38") (pinfunction "D38/A19/SDA1/PWM_38") (pintype "bidirectional"))
    )
    (net (code "187") (name "RES") (class "Default")
      (node (ref "IC1") (pin "18") (pinfunction "~{RESET}_18") (pintype "input"))
      (node (ref "IC2") (pin "18") (pinfunction "~{RESET}_18") (pintype "input"))
      (node (ref "IC3") (pin "18") (pinfunction "~{RESET}_18") (pintype "input"))
      (node (ref "IC4") (pin "18") (pinfunction "~{RESET}_18") (pintype "input"))
      (node (ref "IC5") (pin "18") (pinfunction "~{RESET}_18") (pintype "input"))
      (node (ref "IC6") (pin "18") (pinfunction "~{RESET}_18") (pintype "input"))
      (node (ref "IC7") (pin "18") (pinfunction "~{RESET}_18") (pintype "input"))
      (node (ref "IC8") (pin "18") (pinfunction "~{RESET}_18") (pintype "input"))
      (node (ref "U$1") (pin "23") (pinfunction "D23/A9/TOUCH/PWM_23") (pintype "bidirectional"))
    )
    (net (code "188") (name "SCL") (class "Default")
      (node (ref "IC1") (pin "12") (pinfunction "SCL_12") (pintype "input"))
      (node (ref "IC2") (pin "12") (pinfunction "SCL_12") (pintype "input"))
      (node (ref "IC3") (pin "12") (pinfunction "SCL_12") (pintype "input"))
      (node (ref "IC4") (pin "12") (pinfunction "SCL_12") (pintype "input"))
      (node (ref "IC5") (pin "12") (pinfunction "SCL_12") (pintype "input"))
      (node (ref "IC6") (pin "12") (pinfunction "SCL_12") (pintype "input"))
      (node (ref "IC7") (pin "12") (pinfunction "SCL_12") (pintype "input"))
      (node (ref "IC8") (pin "12") (pinfunction "SCL_12") (pintype "input"))
      (node (ref "R9") (pin "2") (pinfunction "2_2") (pintype "passive"))
      (node (ref "SV25") (pin "2") (pinfunction "2_2") (pintype "passive"))
      (node (ref "U$1") (pin "19") (pinfunction "D19/A5/TOUCH/SCL0_19") (pintype "bidirectional"))
    )
    (net (code "189") (name "SDA") (class "Default")
      (node (ref "IC1") (pin "13") (pinfunction "SDA_13") (pintype "bidirectional"))
      (node (ref "IC2") (pin "13") (pinfunction "SDA_13") (pintype "bidirectional"))
      (node (ref "IC3") (pin "13") (pinfunction "SDA_13") (pintype "bidirectional"))
      (node (ref "IC4") (pin "13") (pinfunction "SDA_13") (pintype "bidirectional"))
      (node (ref "IC5") (pin "13") (pinfunction "SDA_13") (pintype "bidirectional"))
      (node (ref "IC6") (pin "13") (pinfunction "SDA_13") (pintype "bidirectional"))
      (node (ref "IC7") (pin "13") (pinfunction "SDA_13") (pintype "bidirectional"))
      (node (ref "IC8") (pin "13") (pinfunction "SDA_13") (pintype "bidirectional"))
      (node (ref "R1") (pin "2") (pinfunction "2_2") (pintype "passive"))
      (node (ref "SV25") (pin "3") (pinfunction "3_3") (pintype "passive"))
      (node (ref "U$1") (pin "18") (pinfunction "D18/A4/TOUCH/SDA0_18") (pintype "bidirectional"))
    )
    (net (code "190") (name "VIN") (class "Default")
      (node (ref "J12") (pin "1") (pinfunction "1_1") (pintype "bidirectional"))
      (node (ref "U$5") (pin "P$4") (pinfunction "P_P$4") (pintype "passive"))
    )
    (net (code "191") (name "unconnected-(J9-Pad1)") (class "Default")
      (node (ref "J9") (pin "1") (pinfunction "1_1") (pintype "bidirectional"))
    )
    (net (code "192") (name "unconnected-(J9-Pad3)") (class "Default")
      (node (ref "J9") (pin "3") (pinfunction "3_3") (pintype "bidirectional"))
    )
    (net (code "193") (name "unconnected-(J10-Pad1)") (class "Default")
      (node (ref "J10") (pin "1") (pinfunction "1_1") (pintype "bidirectional"))
    )
    (net (code "194") (name "unconnected-(J10-Pad3)") (class "Default")
      (node (ref "J10") (pin "3") (pinfunction "3_3") (pintype "bidirectional"))
    )
    (net (code "195") (name "unconnected-(J11-Pad1)") (class "Default")
      (node (ref "J11") (pin "1") (pinfunction "1_1") (pintype "bidirectional"))
    )
    (net (code "196") (name "unconnected-(J11-Pad3)") (class "Default")
      (node (ref "J11") (pin "3") (pinfunction "3_3") (pintype "bidirectional"))
    )
    (net (code "197") (name "unconnected-(SV3-Pad3)") (class "Default")
      (node (ref "SV3") (pin "3") (pinfunction "3_3") (pintype "passive"))
    )
    (net (code "198") (name "unconnected-(SV6-Pad3)") (class "Default")
      (node (ref "SV6") (pin "3") (pinfunction "3_3") (pintype "passive"))
    )
    (net (code "199") (name "unconnected-(SV9-Pad3)") (class "Default")
      (node (ref "SV9") (pin "3") (pinfunction "3_3") (pintype "passive"))
    )
    (net (code "200") (name "unconnected-(SV12-Pad3)") (class "Default")
      (node (ref "SV12") (pin "3") (pinfunction "3_3") (pintype "passive"))
    )
    (net (code "201") (name "unconnected-(SV15-Pad3)") (class "Default")
      (node (ref "SV15") (pin "3") (pinfunction "3_3") (pintype "passive"))
    )
    (net (code "202") (name "unconnected-(SV18-Pad3)") (class "Default")
      (node (ref "SV18") (pin "3") (pinfunction "3_3") (pintype "passive"))
    )
    (net (code "203") (name "unconnected-(SV21-Pad3)") (class "Default")
      (node (ref "SV21") (pin "3") (pinfunction "3_3") (pintype "passive"))
    )
    (net (code "204") (name "unconnected-(SV24-Pad3)") (class "Default")
      (node (ref "SV24") (pin "3") (pinfunction "3_3") (pintype "passive"))
    )
    (net (code "205") (name "unconnected-(U$1-3V3(MAX_250MILLIA.)-Pad3V3_MAX_250)") (class "Default")
      (node (ref "U$1") (pin "3V3_MAX_250") (pinfunction "3V3(MAX_250MILLIA.)_3V3_MAX_250") (pintype "bidirectional"))
    )
    (net (code "206") (name "unconnected-(U$1-3V3-Pad3.3V_2)") (class "Default")
      (node (ref "U$1") (pin "3.3V_2") (pinfunction "3V3_3.3V_2") (pintype "bidirectional"))
    )
    (net (code "207") (name "unconnected-(U$1-5V-Pad+5V)") (class "Default")
      (node (ref "U$1") (pin "+5V") (pinfunction "5V_+5V") (pintype "bidirectional"))
    )
    (net (code "208") (name "unconnected-(U$1-A21{slash}DAC0-PadA21)") (class "Default")
      (node (ref "U$1") (pin "A21") (pinfunction "A21/DAC0_A21") (pintype "bidirectional"))
    )
    (net (code "209") (name "unconnected-(U$1-A22{slash}DAC1-PadA22)") (class "Default")
      (node (ref "U$1") (pin "A22") (pinfunction "A22/DAC1_A22") (pintype "bidirectional"))
    )
    (net (code "210") (name "unconnected-(U$1-D2{slash}PWM-Pad2)") (class "Default")
      (node (ref "U$1") (pin "2") (pinfunction "D2/PWM_2") (pintype "bidirectional"))
    )
    (net (code "211") (name "unconnected-(U$1-D5{slash}(MISO){slash}(TX1){slash}PWM-Pad5)") (class "Default")
      (node (ref "U$1") (pin "5") (pinfunction "D5/(MISO)/(TX1)/PWM_5") (pintype "bidirectional"))
    )
    (net (code "212") (name "unconnected-(U$1-D6{slash}PWM-Pad6)") (class "Default")
      (node (ref "U$1") (pin "6") (pinfunction "D6/PWM_6") (pintype "bidirectional"))
    )
    (net (code "213") (name "unconnected-(U$1-D7{slash}(SCL0){slash}(MOSI0){slash}RX3{slash}PWM-Pad7)") (class "Default")
      (node (ref "U$1") (pin "7") (pinfunction "D7/(SCL0)/(MOSI0)/RX3/PWM_7") (pintype "bidirectional"))
    )
    (net (code "214") (name "unconnected-(U$1-D8{slash}(SDA0){slash}(MISO0){slash}TX3{slash}PWM-Pad8)") (class "Default")
      (node (ref "U$1") (pin "8") (pinfunction "D8/(SDA0)/(MISO0)/TX3/PWM_8") (pintype "bidirectional"))
    )
    (net (code "215") (name "unconnected-(U$1-D14{slash}A0{slash}(SCK0){slash}PWM-Pad14)") (class "Default")
      (node (ref "U$1") (pin "14") (pinfunction "D14/A0/(SCK0)/PWM_14") (pintype "bidirectional"))
    )
    (net (code "216") (name "unconnected-(U$1-D15{slash}A1{slash}TOUCH{slash}CS0-Pad15)") (class "Default")
      (node (ref "U$1") (pin "15") (pinfunction "D15/A1/TOUCH/CS0_15") (pintype "bidirectional"))
    )
    (net (code "217") (name "unconnected-(U$1-D17{slash}A3{slash}TOUCH{slash}(SDA0)-Pad17)") (class "Default")
      (node (ref "U$1") (pin "17") (pinfunction "D17/A3/TOUCH/(SDA0)_17") (pintype "bidirectional"))
    )
    (net (code "218") (name "unconnected-(U$1-D20{slash}A6{slash}CS0{slash}(SCK1){slash}PWM-Pad20)") (class "Default")
      (node (ref "U$1") (pin "20") (pinfunction "D20/A6/CS0/(SCK1)/PWM_20") (pintype "bidirectional"))
    )
    (net (code "219") (name "unconnected-(U$1-D21{slash}A7{slash}CS0{slash}(MOSI1){slash}PWM-Pad21)") (class "Default")
      (node (ref "U$1") (pin "21") (pinfunction "D21/A7/CS0/(MOSI1)/PWM_21") (pintype "bidirectional"))
    )
    (net (code "220") (name "unconnected-(U$1-D22{slash}A8{slash}TOUCH{slash}PWM-Pad22)") (class "Default")
      (node (ref "U$1") (pin "22") (pinfunction "D22/A8/TOUCH/PWM_22") (pintype "bidirectional"))
    )
    (net (code "221") (name "unconnected-(U$1-D28-Pad28)") (class "Default")
      (node (ref "U$1") (pin "28") (pinfunction "D28_28") (pintype "bidirectional"))
    )
    (net (code "222") (name "unconnected-(U$1-D29{slash}TOUCH{slash}(CAN0TX){slash}PWM-Pad29)") (class "Default")
      (node (ref "U$1") (pin "29") (pinfunction "D29/TOUCH/(CAN0TX)/PWM_29") (pintype "bidirectional"))
    )
    (net (code "223") (name "unconnected-(U$1-D30{slash}TOUCH{slash}(CAN0RX){slash}PWM-Pad30)") (class "Default")
      (node (ref "U$1") (pin "30") (pinfunction "D30/TOUCH/(CAN0RX)/PWM_30") (pintype "bidirectional"))
    )
    (net (code "224") (name "unconnected-(U$1-D31{slash}A12{slash}CS1{slash}RX4-Pad31)") (class "Default")
      (node (ref "U$1") (pin "31") (pinfunction "D31/A12/CS1/RX4_31") (pintype "bidirectional"))
    )
    (net (code "225") (name "unconnected-(U$1-D32{slash}A13{slash}SCK1{slash}TX4-Pad32)") (class "Default")
      (node (ref "U$1") (pin "32") (pinfunction "D32/A13/SCK1/TX4_32") (pintype "bidirectional"))
    )
    (net (code "226") (name "unconnected-(U$1-D33{slash}A14{slash}CAN1TX{slash}(SCL0)-Pad33)") (class "Default")
      (node (ref "U$1") (pin "33") (pinfunction "D33/A14/CAN1TX/(SCL0)_33") (pintype "bidirectional"))
    )
    (net (code "227") (name "unconnected-(U$1-D34{slash}A15{slash}CAN1RX{slash}(SDA0)-Pad34)") (class "Default")
      (node (ref "U$1") (pin "34") (pinfunction "D34/A15/CAN1RX/(SDA0)_34") (pintype "bidirectional"))
    )
    (net (code "228") (name "unconnected-(U$1-D35{slash}A16{slash}PWM-Pad35)") (class "Default")
      (node (ref "U$1") (pin "35") (pinfunction "D35/A16/PWM_35") (pintype "bidirectional"))
    )
    (net (code "229") (name "unconnected-(U$1-D36{slash}A17{slash}PWM-Pad36)") (class "Default")
      (node (ref "U$1") (pin "36") (pinfunction "D36/A17/PWM_36") (pintype "bidirectional"))
    )
    (net (code "230") (name "unconnected-(U$1-GND-PadGND3)") (class "Default")
      (node (ref "U$1") (pin "GND3") (pinfunction "GND_GND3") (pintype "bidirectional"))
    )
    (net (code "231") (name "unconnected-(U$1-GND-PadGND4)") (class "Default")
      (node (ref "U$1") (pin "GND4") (pinfunction "GND_GND4") (pintype "bidirectional"))
    )
    (net (code "232") (name "unconnected-(U$1-GND-PadGND5)") (class "Default")
      (node (ref "U$1") (pin "GND5") (pinfunction "GND_GND5") (pintype "bidirectional"))
    )
    (net (code "233") (name "unconnected-(U$1-PadA10)") (class "Default")
      (node (ref "U$1") (pin "A10") (pinfunction "A10_A10") (pintype "bidirectional"))
    )
    (net (code "234") (name "unconnected-(U$1-PadA11)") (class "Default")
      (node (ref "U$1") (pin "A11") (pinfunction "A11_A11") (pintype "bidirectional"))
    )
    (net (code "235") (name "unconnected-(U$1-PadAREF)") (class "Default")
      (node (ref "U$1") (pin "AREF") (pinfunction "AREF_AREF") (pintype "bidirectional"))
    )
    (net (code "236") (name "unconnected-(U$1-PadD+)") (class "Default")
      (node (ref "U$1") (pin "D+") (pinfunction "D+_D+") (pintype "bidirectional"))
    )
    (net (code "237") (name "unconnected-(U$1-PadD-)") (class "Default")
      (node (ref "U$1") (pin "D-") (pinfunction "D-_D-") (pintype "bidirectional"))
    )
    (net (code "238") (name "unconnected-(U$1-PadPROGRAM)") (class "Default")
      (node (ref "U$1") (pin "PROGRAM") (pinfunction "PROGRAM_PROGRAM") (pintype "bidirectional"))
    )
    (net (code "239") (name "unconnected-(U$1-PadRESET)") (class "Default")
      (node (ref "U$1") (pin "RESET") (pinfunction "RESET_RESET") (pintype "bidirectional"))
    )
    (net (code "240") (name "unconnected-(U$1-PadVUSB)") (class "Default")
      (node (ref "U$1") (pin "VUSB") (pinfunction "VUSB_VUSB") (pintype "bidirectional"))
    )
    (net (code "241") (name "unconnected-(U$1-VBAT(3V_COIN_CELL_FOR_RTC)-PadVBAT)") (class "Default")
      (node (ref "U$1") (pin "VBAT") (pinfunction "VBAT(3V_COIN_CELL_FOR_RTC)_VBAT") (pintype "bidirectional"))
    )
  )
)
